# FPGA_MICS_SUP.net
KiCad netlist of a schematic drawn in Altium Designer
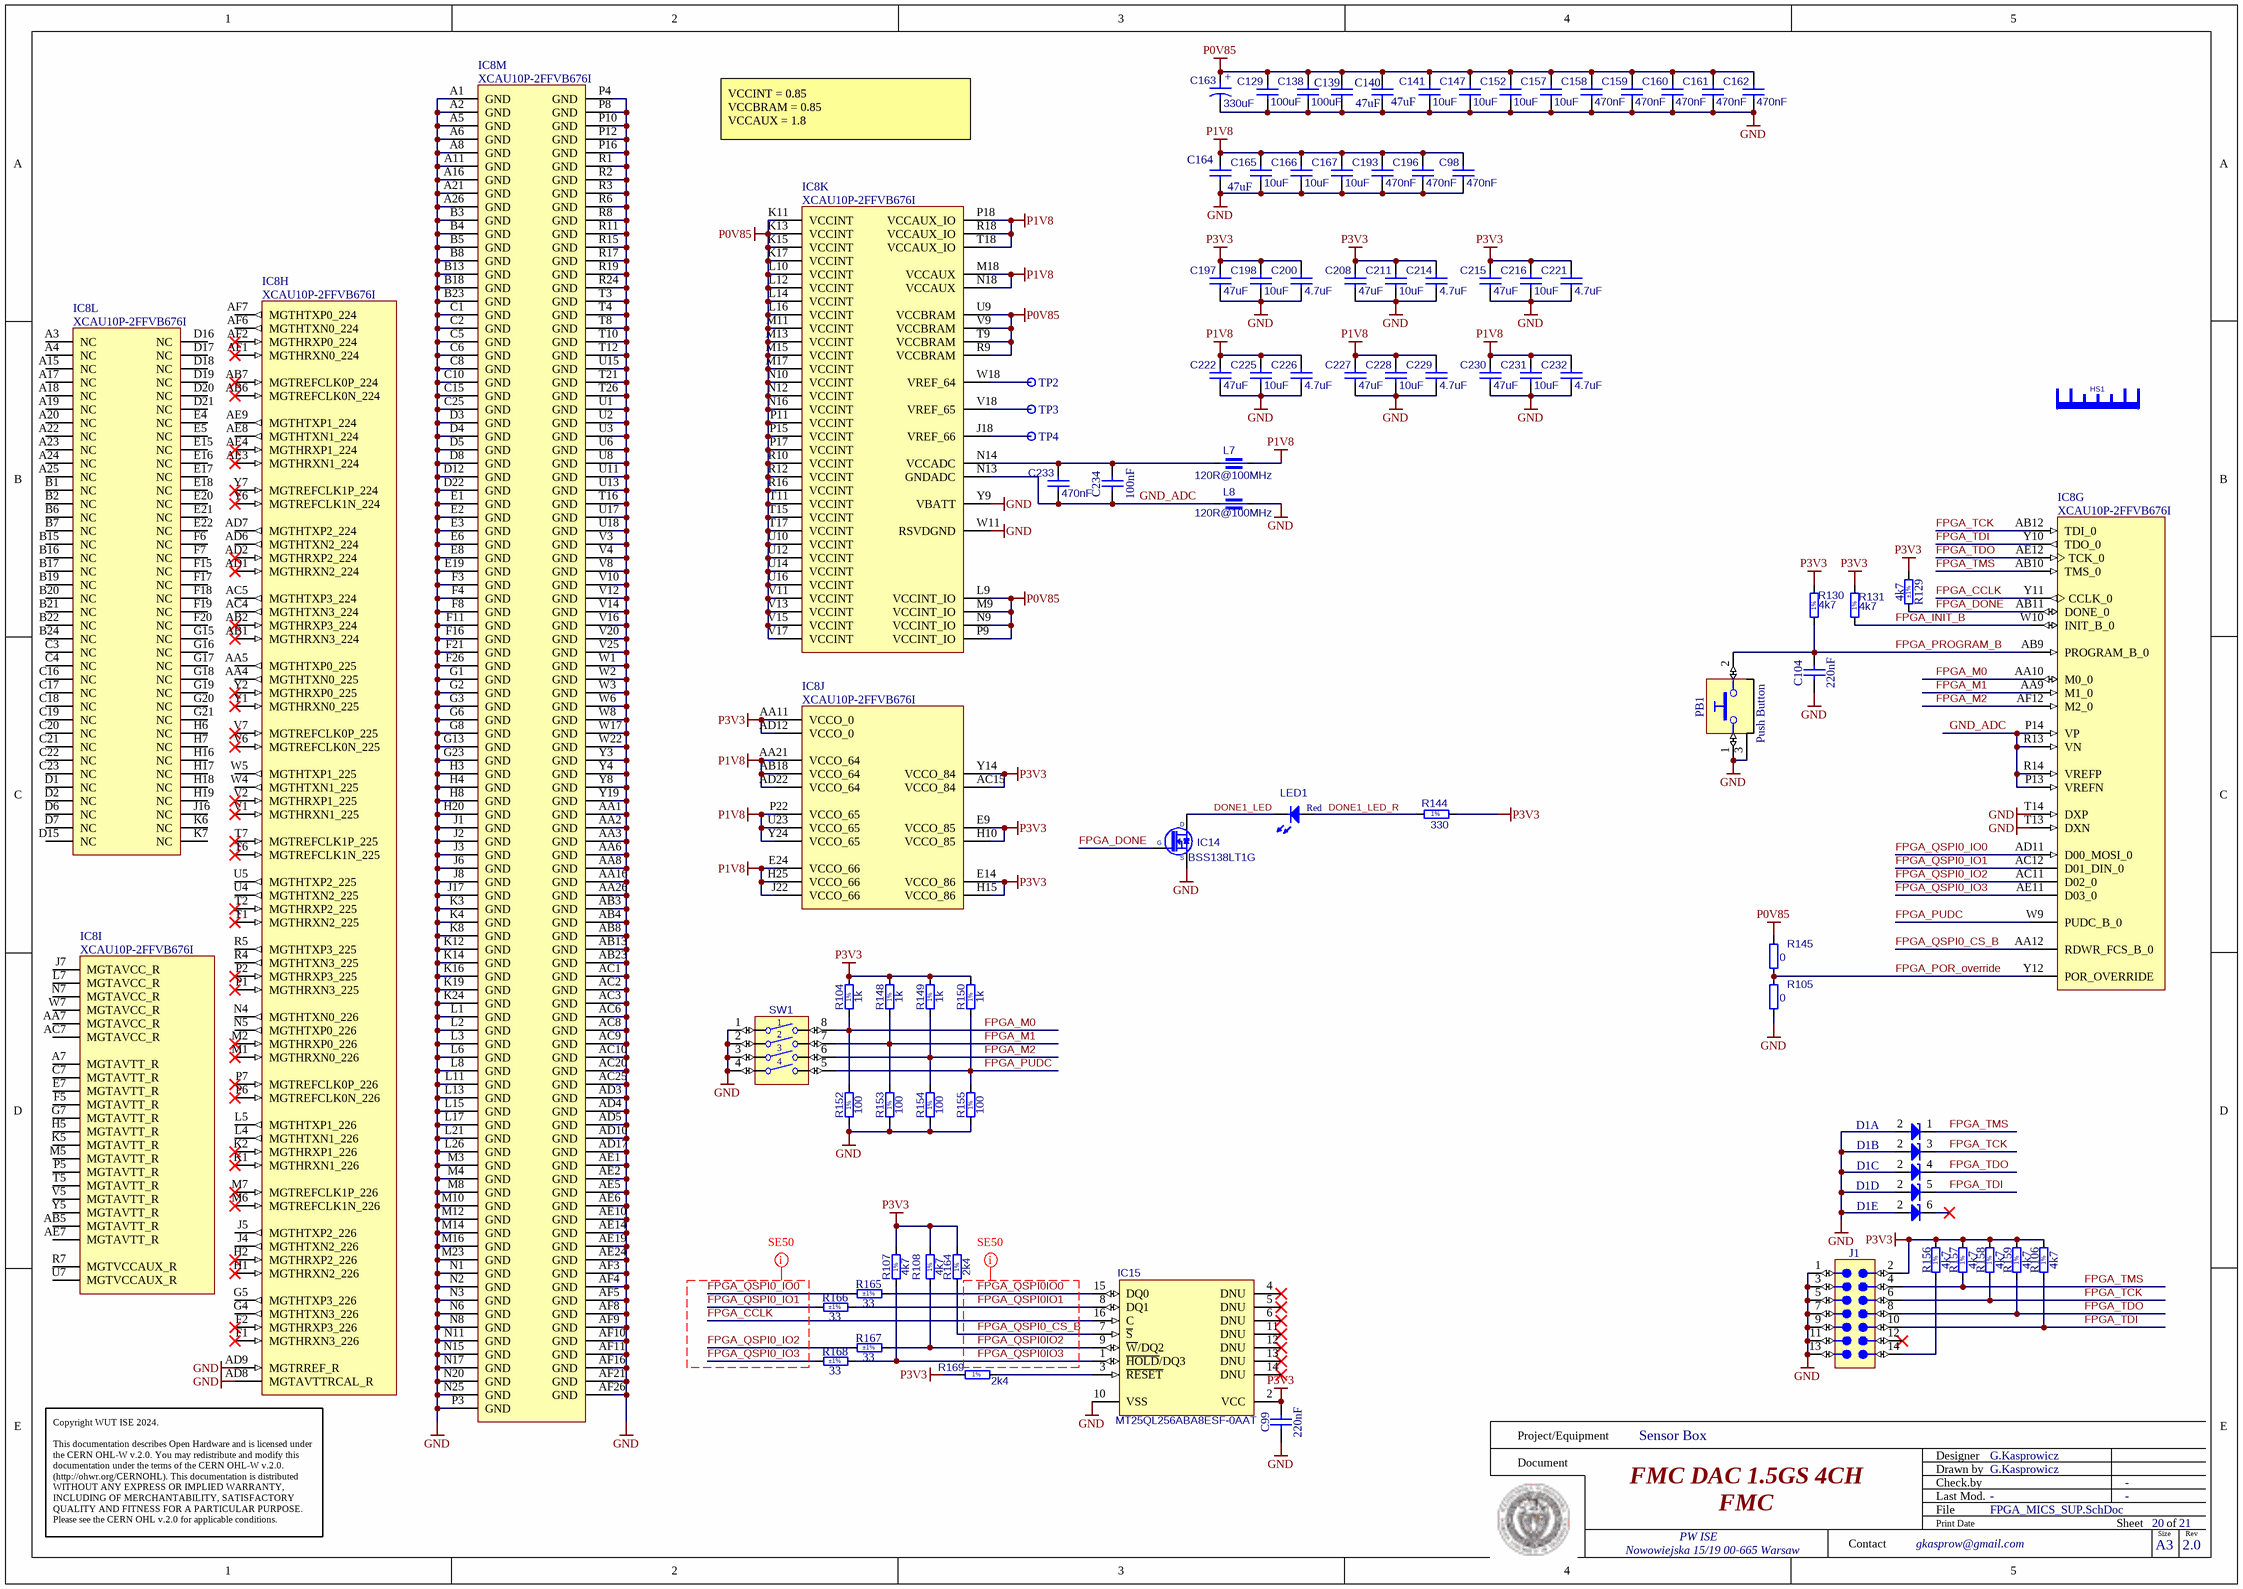
[diagram p0: FPGA_MICS_SUP.SchDoc]

(export (version "E")
  (design (tool "Eeschema 10.0.6"))
  (components
    (comp (ref "C98")
      (value "470nF")
      (footprint "CAPC0603X33N")
      (description "Non-polarised capacitor")
      (fields
        (field (name "PART NUMBER") "CC0201_470NF_4V_20%_X5R")
        (field (name "VOLTAGE") "4V")
        (field (name "AUTHOR") "CERN DEM JLC")
      )
      (libsource (lib "Capacitors") (part "Capacitor - non polarized"))
    )
    (comp (ref "C99")
      (value "220nF")
      (footprint "CAPC1005X55N")
      (description "Non-polarised capacitor")
      (fields
        (field (name "PART NUMBER") "CC0402_220NF_16V_10%_X7R")
        (field (name "VOLTAGE") "16V")
        (field (name "AUTHOR") "CERN DEM JLC")
      )
      (libsource (lib "Capacitors") (part "Capacitor - non polarized"))
    )
    (comp (ref "C104")
      (value "220nF")
      (footprint "CAPC1005X55N")
      (description "Non-polarised capacitor")
      (fields
        (field (name "PART NUMBER") "CC0402_220NF_16V_10%_X7R")
        (field (name "VOLTAGE") "16V")
        (field (name "AUTHOR") "CERN DEM JLC")
      )
      (libsource (lib "Capacitors") (part "Capacitor - non polarized"))
    )
    (comp (ref "C129")
      (value "100uF")
      (footprint "CAPC2013X145N")
      (description "Non-polarised capacitor")
      (fields
        (field (name "PART NUMBER") "CC0805_100UF_4V_20%_X6S_MURATA_GRM21BC80G107ME15")
        (field (name "VOLTAGE") "4V")
        (field (name "AUTHOR") "CERN DEM BC")
      )
      (libsource (lib "Capacitors") (part "Capacitor - non polarized"))
    )
    (comp (ref "C138")
      (value "100uF")
      (footprint "CAPC2013X145N")
      (description "Non-polarised capacitor")
      (fields
        (field (name "PART NUMBER") "CC0805_100UF_4V_20%_X6S_MURATA_GRM21BC80G107ME15")
        (field (name "VOLTAGE") "4V")
        (field (name "AUTHOR") "CERN DEM BC")
      )
      (libsource (lib "Capacitors") (part "Capacitor - non polarized"))
    )
    (comp (ref "C139")
      (value "47uF")
      (footprint "CAPC1608X100N")
      (description "Non-polarised capacitor")
      (fields
        (field (name "MANUFACTURER PART NUMBER") "CC0603_47UF_6.3V_20%_X5R")
        (field (name "MANUFACTURER") "GENERIC")
        (field (name "AUTHOR") "CERN DEM JLC")
      )
      (libsource (lib "Capacitors") (part "Capacitor - non polarized"))
    )
    (comp (ref "C140")
      (value "47uF")
      (footprint "CAPC1608X100N")
      (description "Non-polarised capacitor")
      (fields
        (field (name "MANUFACTURER PART NUMBER") "CC0603_47UF_6.3V_20%_X5R")
        (field (name "MANUFACTURER") "GENERIC")
        (field (name "AUTHOR") "CERN DEM JLC")
      )
      (libsource (lib "Capacitors") (part "Capacitor - non polarized"))
    )
    (comp (ref "C141")
      (value "10uF")
      (footprint "CAPC1005X70N")
      (description "Non-polarised capacitor")
      (fields
        (field (name "PART NUMBER") "CC0402_10UF_6.3V_20%_X5R")
        (field (name "VOLTAGE") "6.3V")
        (field (name "AUTHOR") "CERN DEM JLC")
      )
      (libsource (lib "Capacitors") (part "Capacitor - non polarized"))
    )
    (comp (ref "C147")
      (value "10uF")
      (footprint "CAPC1005X70N")
      (description "Non-polarised capacitor")
      (fields
        (field (name "PART NUMBER") "CC0402_10UF_6.3V_20%_X5R")
        (field (name "VOLTAGE") "6.3V")
        (field (name "AUTHOR") "CERN DEM JLC")
      )
      (libsource (lib "Capacitors") (part "Capacitor - non polarized"))
    )
    (comp (ref "C152")
      (value "10uF")
      (footprint "CAPC1005X70N")
      (description "Non-polarised capacitor")
      (fields
        (field (name "PART NUMBER") "CC0402_10UF_6.3V_20%_X5R")
        (field (name "VOLTAGE") "6.3V")
        (field (name "AUTHOR") "CERN DEM JLC")
      )
      (libsource (lib "Capacitors") (part "Capacitor - non polarized"))
    )
    (comp (ref "C157")
      (value "10uF")
      (footprint "CAPC1005X70N")
      (description "Non-polarised capacitor")
      (fields
        (field (name "PART NUMBER") "CC0402_10UF_6.3V_20%_X5R")
        (field (name "VOLTAGE") "6.3V")
        (field (name "AUTHOR") "CERN DEM JLC")
      )
      (libsource (lib "Capacitors") (part "Capacitor - non polarized"))
    )
    (comp (ref "C158")
      (value "470nF")
      (footprint "CAPC0603X33N")
      (description "Non-polarised capacitor")
      (fields
        (field (name "PART NUMBER") "CC0201_470NF_4V_20%_X5R")
        (field (name "VOLTAGE") "4V")
        (field (name "AUTHOR") "CERN DEM JLC")
      )
      (libsource (lib "Capacitors") (part "Capacitor - non polarized"))
    )
    (comp (ref "C159")
      (value "470nF")
      (footprint "CAPC0603X33N")
      (description "Non-polarised capacitor")
      (fields
        (field (name "PART NUMBER") "CC0201_470NF_4V_20%_X5R")
        (field (name "VOLTAGE") "4V")
        (field (name "AUTHOR") "CERN DEM JLC")
      )
      (libsource (lib "Capacitors") (part "Capacitor - non polarized"))
    )
    (comp (ref "C160")
      (value "470nF")
      (footprint "CAPC0603X33N")
      (description "Non-polarised capacitor")
      (fields
        (field (name "PART NUMBER") "CC0201_470NF_4V_20%_X5R")
        (field (name "VOLTAGE") "4V")
        (field (name "AUTHOR") "CERN DEM JLC")
      )
      (libsource (lib "Capacitors") (part "Capacitor - non polarized"))
    )
    (comp (ref "C161")
      (value "470nF")
      (footprint "CAPC0603X33N")
      (description "Non-polarised capacitor")
      (fields
        (field (name "PART NUMBER") "CC0201_470NF_4V_20%_X5R")
        (field (name "VOLTAGE") "4V")
        (field (name "AUTHOR") "CERN DEM JLC")
      )
      (libsource (lib "Capacitors") (part "Capacitor - non polarized"))
    )
    (comp (ref "C162")
      (value "470nF")
      (footprint "CAPC0603X33N")
      (description "Non-polarised capacitor")
      (fields
        (field (name "PART NUMBER") "CC0201_470NF_4V_20%_X5R")
        (field (name "VOLTAGE") "4V")
        (field (name "AUTHOR") "CERN DEM JLC")
      )
      (libsource (lib "Capacitors") (part "Capacitor - non polarized"))
    )
    (comp (ref "C163")
      (value "330uF")
      (footprint "CAPMP3528X210N")
      (description "Polarised capacitor")
      (fields
        (field (name "PART NUMBER") "CTE3528-21_330UF_2.5V_20%_LESR0015_KEMET_T520")
        (field (name "VOLTAGE") "2.5V")
        (field (name "AUTHOR") "CERN DEM JLC")
      )
      (libsource (lib "Capacitors") (part "Capacitor - polarized"))
    )
    (comp (ref "C164")
      (value "47uF")
      (footprint "CAPC1608X100N")
      (description "Non-polarised capacitor")
      (fields
        (field (name "MANUFACTURER PART NUMBER") "CC0603_47UF_6.3V_20%_X5R")
        (field (name "MANUFACTURER") "GENERIC")
        (field (name "AUTHOR") "CERN DEM JLC")
      )
      (libsource (lib "Capacitors") (part "Capacitor - non polarized"))
    )
    (comp (ref "C165")
      (value "10uF")
      (footprint "CAPC1005X70N")
      (description "Non-polarised capacitor")
      (fields
        (field (name "PART NUMBER") "CC0402_10UF_6.3V_20%_X5R")
        (field (name "VOLTAGE") "6.3V")
        (field (name "AUTHOR") "CERN DEM JLC")
      )
      (libsource (lib "Capacitors") (part "Capacitor - non polarized"))
    )
    (comp (ref "C166")
      (value "10uF")
      (footprint "CAPC1005X70N")
      (description "Non-polarised capacitor")
      (fields
        (field (name "PART NUMBER") "CC0402_10UF_6.3V_20%_X5R")
        (field (name "VOLTAGE") "6.3V")
        (field (name "AUTHOR") "CERN DEM JLC")
      )
      (libsource (lib "Capacitors") (part "Capacitor - non polarized"))
    )
    (comp (ref "C167")
      (value "10uF")
      (footprint "CAPC1005X70N")
      (description "Non-polarised capacitor")
      (fields
        (field (name "PART NUMBER") "CC0402_10UF_6.3V_20%_X5R")
        (field (name "VOLTAGE") "6.3V")
        (field (name "AUTHOR") "CERN DEM JLC")
      )
      (libsource (lib "Capacitors") (part "Capacitor - non polarized"))
    )
    (comp (ref "C193")
      (value "470nF")
      (footprint "CAPC0603X33N")
      (description "Non-polarised capacitor")
      (fields
        (field (name "PART NUMBER") "CC0201_470NF_4V_20%_X5R")
        (field (name "VOLTAGE") "4V")
        (field (name "AUTHOR") "CERN DEM JLC")
      )
      (libsource (lib "Capacitors") (part "Capacitor - non polarized"))
    )
    (comp (ref "C196")
      (value "470nF")
      (footprint "CAPC0603X33N")
      (description "Non-polarised capacitor")
      (fields
        (field (name "PART NUMBER") "CC0201_470NF_4V_20%_X5R")
        (field (name "VOLTAGE") "4V")
        (field (name "AUTHOR") "CERN DEM JLC")
      )
      (libsource (lib "Capacitors") (part "Capacitor - non polarized"))
    )
    (comp (ref "C197")
      (value "47uF")
      (footprint "CAPC1608X100N")
      (description "Non-polarised capacitor")
      (fields
        (field (name "PART NUMBER") "CC0603_47UF_6.3V_20%_X5R")
        (field (name "VOLTAGE") "6.3V")
        (field (name "AUTHOR") "CERN DEM JLC")
      )
      (libsource (lib "Capacitors") (part "Capacitor - non polarized"))
    )
    (comp (ref "C198")
      (value "10uF")
      (footprint "CAPC1005X70N")
      (description "Non-polarised capacitor")
      (fields
        (field (name "PART NUMBER") "CC0402_10UF_6.3V_20%_X5R")
        (field (name "VOLTAGE") "6.3V")
        (field (name "AUTHOR") "CERN DEM JLC")
      )
      (libsource (lib "Capacitors") (part "Capacitor - non polarized"))
    )
    (comp (ref "C200")
      (value "4.7uF")
      (footprint "CAPC1005X61N")
      (description "Non-polarised capacitor")
      (fields
        (field (name "PART NUMBER") "CC0402_4.7UF_4V_20%_X6S_TDK_C1005X6S0G475M050BC")
        (field (name "VOLTAGE") "4V")
        (field (name "AUTHOR") "CERN DEM BC")
      )
      (libsource (lib "Capacitors") (part "Capacitor - non polarized"))
    )
    (comp (ref "C208")
      (value "47uF")
      (footprint "CAPC1608X100N")
      (description "Non-polarised capacitor")
      (fields
        (field (name "PART NUMBER") "CC0603_47UF_6.3V_20%_X5R")
        (field (name "VOLTAGE") "6.3V")
        (field (name "AUTHOR") "CERN DEM JLC")
      )
      (libsource (lib "Capacitors") (part "Capacitor - non polarized"))
    )
    (comp (ref "C211")
      (value "10uF")
      (footprint "CAPC1005X70N")
      (description "Non-polarised capacitor")
      (fields
        (field (name "PART NUMBER") "CC0402_10UF_6.3V_20%_X5R")
        (field (name "VOLTAGE") "6.3V")
        (field (name "AUTHOR") "CERN DEM JLC")
      )
      (libsource (lib "Capacitors") (part "Capacitor - non polarized"))
    )
    (comp (ref "C214")
      (value "4.7uF")
      (footprint "CAPC1005X61N")
      (description "Non-polarised capacitor")
      (fields
        (field (name "PART NUMBER") "CC0402_4.7UF_4V_20%_X6S_TDK_C1005X6S0G475M050BC")
        (field (name "VOLTAGE") "4V")
        (field (name "AUTHOR") "CERN DEM BC")
      )
      (libsource (lib "Capacitors") (part "Capacitor - non polarized"))
    )
    (comp (ref "C215")
      (value "47uF")
      (footprint "CAPC1608X100N")
      (description "Non-polarised capacitor")
      (fields
        (field (name "PART NUMBER") "CC0603_47UF_6.3V_20%_X5R")
        (field (name "VOLTAGE") "6.3V")
        (field (name "AUTHOR") "CERN DEM JLC")
      )
      (libsource (lib "Capacitors") (part "Capacitor - non polarized"))
    )
    (comp (ref "C216")
      (value "10uF")
      (footprint "CAPC1005X70N")
      (description "Non-polarised capacitor")
      (fields
        (field (name "PART NUMBER") "CC0402_10UF_6.3V_20%_X5R")
        (field (name "VOLTAGE") "6.3V")
        (field (name "AUTHOR") "CERN DEM JLC")
      )
      (libsource (lib "Capacitors") (part "Capacitor - non polarized"))
    )
    (comp (ref "C221")
      (value "4.7uF")
      (footprint "CAPC1005X61N")
      (description "Non-polarised capacitor")
      (fields
        (field (name "PART NUMBER") "CC0402_4.7UF_4V_20%_X6S_TDK_C1005X6S0G475M050BC")
        (field (name "VOLTAGE") "4V")
        (field (name "AUTHOR") "CERN DEM BC")
      )
      (libsource (lib "Capacitors") (part "Capacitor - non polarized"))
    )
    (comp (ref "C222")
      (value "47uF")
      (footprint "CAPC1608X100N")
      (description "Non-polarised capacitor")
      (fields
        (field (name "PART NUMBER") "CC0603_47UF_6.3V_20%_X5R")
        (field (name "VOLTAGE") "6.3V")
        (field (name "AUTHOR") "CERN DEM JLC")
      )
      (libsource (lib "Capacitors") (part "Capacitor - non polarized"))
    )
    (comp (ref "C225")
      (value "10uF")
      (footprint "CAPC1005X70N")
      (description "Non-polarised capacitor")
      (fields
        (field (name "PART NUMBER") "CC0402_10UF_6.3V_20%_X5R")
        (field (name "VOLTAGE") "6.3V")
        (field (name "AUTHOR") "CERN DEM JLC")
      )
      (libsource (lib "Capacitors") (part "Capacitor - non polarized"))
    )
    (comp (ref "C226")
      (value "4.7uF")
      (footprint "CAPC1005X61N")
      (description "Non-polarised capacitor")
      (fields
        (field (name "PART NUMBER") "CC0402_4.7UF_4V_20%_X6S_TDK_C1005X6S0G475M050BC")
        (field (name "VOLTAGE") "4V")
        (field (name "AUTHOR") "CERN DEM BC")
      )
      (libsource (lib "Capacitors") (part "Capacitor - non polarized"))
    )
    (comp (ref "C227")
      (value "47uF")
      (footprint "CAPC1608X100N")
      (description "Non-polarised capacitor")
      (fields
        (field (name "PART NUMBER") "CC0603_47UF_6.3V_20%_X5R")
        (field (name "VOLTAGE") "6.3V")
        (field (name "AUTHOR") "CERN DEM JLC")
      )
      (libsource (lib "Capacitors") (part "Capacitor - non polarized"))
    )
    (comp (ref "C228")
      (value "10uF")
      (footprint "CAPC1005X70N")
      (description "Non-polarised capacitor")
      (fields
        (field (name "PART NUMBER") "CC0402_10UF_6.3V_20%_X5R")
        (field (name "VOLTAGE") "6.3V")
        (field (name "AUTHOR") "CERN DEM JLC")
      )
      (libsource (lib "Capacitors") (part "Capacitor - non polarized"))
    )
    (comp (ref "C229")
      (value "4.7uF")
      (footprint "CAPC1005X61N")
      (description "Non-polarised capacitor")
      (fields
        (field (name "PART NUMBER") "CC0402_4.7UF_4V_20%_X6S_TDK_C1005X6S0G475M050BC")
        (field (name "VOLTAGE") "4V")
        (field (name "AUTHOR") "CERN DEM BC")
      )
      (libsource (lib "Capacitors") (part "Capacitor - non polarized"))
    )
    (comp (ref "C230")
      (value "47uF")
      (footprint "CAPC1608X100N")
      (description "Non-polarised capacitor")
      (fields
        (field (name "PART NUMBER") "CC0603_47UF_6.3V_20%_X5R")
        (field (name "VOLTAGE") "6.3V")
        (field (name "AUTHOR") "CERN DEM JLC")
      )
      (libsource (lib "Capacitors") (part "Capacitor - non polarized"))
    )
    (comp (ref "C231")
      (value "10uF")
      (footprint "CAPC1005X70N")
      (description "Non-polarised capacitor")
      (fields
        (field (name "PART NUMBER") "CC0402_10UF_6.3V_20%_X5R")
        (field (name "VOLTAGE") "6.3V")
        (field (name "AUTHOR") "CERN DEM JLC")
      )
      (libsource (lib "Capacitors") (part "Capacitor - non polarized"))
    )
    (comp (ref "C232")
      (value "4.7uF")
      (footprint "CAPC1005X61N")
      (description "Non-polarised capacitor")
      (fields
        (field (name "PART NUMBER") "CC0402_4.7UF_4V_20%_X6S_TDK_C1005X6S0G475M050BC")
        (field (name "VOLTAGE") "4V")
        (field (name "AUTHOR") "CERN DEM BC")
      )
      (libsource (lib "Capacitors") (part "Capacitor - non polarized"))
    )
    (comp (ref "C233")
      (value "470nF")
      (footprint "CAPC0603X33N")
      (description "Non-polarised capacitor")
      (fields
        (field (name "PART NUMBER") "CC0201_470NF_4V_20%_X5R")
        (field (name "VOLTAGE") "4V")
        (field (name "AUTHOR") "CERN DEM JLC")
      )
      (libsource (lib "Capacitors") (part "Capacitor - non polarized"))
    )
    (comp (ref "C234")
      (value "100nF")
      (footprint "CAPC1005X55N")
      (description "Non-polarised capacitor")
      (fields
        (field (name "PART NUMBER") "CC0402_100NF_16V_10%_X5R")
        (field (name "VOLTAGE") "16V")
        (field (name "AUTHOR") "CERN DEM JLC")
      )
      (libsource (lib "Capacitors") (part "Capacitor - non polarized"))
    )
    (comp (ref "D1")
      (value "PESD3V3L5UY")
      (footprint "SOT65P210X110-6N")
      (description "Fivefold ESD Protection Diode Arrays")
      (fields
        (field (name "VOLTAGE") "3.3V")
        (field (name "POWER") "200W")
        (field (name "AUTHOR") "CERN DEM WB")
      )
      (libsource (lib "ICs And Semiconductors") (part "PESD Array 5diodes 6pins Common anode2"))
    )
    (comp (ref "HS1")
      (value "Heat Sink 2 Pads")
      (footprint "HSINK_WAKEFIELD_960-29-18-D-AB-0")
      (description "Heat Sink With 2 pads")
      (fields
        (field (name "PART NUMBER") "HSINK_WAKEFIELD_960-29-12-D-AB-0")
        (field (name "MANUFACTURER") "WAKEFIELD-VETTE")
        (field (name "AUTHOR") "CERN DEM BC")
      )
      (libsource (lib "Eletro-mechanical") (part "Heat Sink 2 Pads"))
    )
    (comp (ref "IC8")
      (value "XCAU10P-2FFVB676I")
      (footprint "BGA676C100P26X26_2700X2700X350")
      (description "Artix UltraScale + Field Programmable Gate Array (FPGA), 676-Pin BGA, Industrial Grade")
      (fields (field (name "MANUFACTURER") "AMD") (field (name "AUTHOR") "CERN DEM HF"))
      (libsource (lib "ICs And Semiconductors") (part "XCAU10P-2FFVB676I"))
    )
    (comp (ref "IC14")
      (value "BSS138LT1G")
      (footprint "SOT95P240X110-3N")
      (description "N-CHANNEL MOSFET WITH DIODE")
      (fields (field (name "MANUFACTURER") "ON SEMICONDUCTOR") (field (name "AUTHOR") "CERN DEM JLC"))
      (libsource (lib "ICs And Semiconductors") (part "N-MOSFET-D 1G 2S 3D"))
    )
    (comp (ref "IC15")
      (value "MT25QL256ABA8ESF-0AAT")
      (footprint "SOIC127P1030X265-16N")
      (description "256Mbit (32MB), 2.7V-3.6V, Multiple I/O Serial NOR Flash Memory,with Reset# & Hold#")
      (fields (field (name "MANUFACTURER") "MICRON TECHNOLOGY") (field (name "AUTHOR") "CERN DEM JLC"))
      (libsource (lib "ICs And Semiconductors") (part "MT25QL256ABA8ESF"))
    )
    (comp (ref "J1")
      (value "~")
      (footprint "MOLEX_87832-1420")
      (description "Connector 14 Male")
      (fields
        (field (name "PART NUMBER") "MOLEX_87832-1420")
        (field (name "MANUFACTURER") "MOLEX")
        (field (name "AUTHOR") "CERN DEM JLC")
      )
      (libsource (lib "Connectors") (part "Connector 14 Male"))
    )
    (comp (ref "L7")
      (value "120R@100MHz")
      (footprint "INDC1608X95N")
      (fields
        (field (name "PART NUMBER") "IND0603_MURATA_BLM18PG121SN1D")
        (field (name "POWER") "2A")
        (field (name "MANUFACTURER") "MURATA")
        (field (name "AUTHOR") "CERN DEM BC")
      )
      (libsource (lib "Inductors & Transformers") (part "Ferrite Bead"))
    )
    (comp (ref "L8")
      (value "120R@100MHz")
      (footprint "INDC1608X95N")
      (fields
        (field (name "PART NUMBER") "IND0603_MURATA_BLM18PG121SN1D")
        (field (name "POWER") "2A")
        (field (name "MANUFACTURER") "MURATA")
        (field (name "AUTHOR") "CERN DEM BC")
      )
      (libsource (lib "Inductors & Transformers") (part "Ferrite Bead"))
    )
    (comp (ref "LED1")
      (value "Red")
      (footprint "LED_KINGBRIGHT_KPH-1608SURCK")
      (description "LED Red 1C 2A")
      (fields
        (field (name "PART NUMBER") "LED_KINGBRIGHT_KPH-1608SURCK")
        (field (name "MANUFACTURER") "KINGBRIGHT")
        (field (name "AUTHOR") "CERN DEM JLC")
      )
      (libsource (lib "ICs And Semiconductors") (part "LED Red 1C 2A"))
    )
    (comp (ref "PB1")
      (value "Push Button")
      (footprint "PB_OMRON_B3U-1100P")
      (description "Push-Button Switch SPDT")
      (fields
        (field (name "PART NUMBER") "PB_OMRON_B3U-1100P")
        (field (name "MANUFACTURER") "OMRON")
        (field (name "AUTHOR") "CERN DEM JLC")
      )
      (libsource (lib "Eletro-mechanical") (part "PB SPST 1NO-2NO 3CASE"))
    )
    (comp (ref "R104")
      (value "1k")
      (footprint "RESC1005X40N")
      (description "Resistor - 1%")
      (fields
        (field (name "PART NUMBER") "R0402_1K_1%_0.0625W_100PPM")
        (field (name "POWER") "0.0625W")
        (field (name "AUTHOR") "CERN DEM JLC")
      )
      (libsource (lib "Resistors") (part "Resistor - 1%"))
    )
    (comp (ref "R105")
      (value "0")
      (footprint "RESC1005X40N")
      (description "Resistor")
      (fields
        (field (name "MANUFACTURER PART NUMBER") "R0402_0R_JUMPER")
        (field (name "MANUFACTURER") "GENERIC")
        (field (name "AUTHOR") "CERN DEM JLC")
      )
      (libsource (lib "Resistors") (part "Resistor"))
    )
    (comp (ref "R106")
      (value "4k7")
      (footprint "RESC1005X40N")
      (description "Resistor - 1%")
      (fields
        (field (name "PART NUMBER") "R0402_4K7_1%_0.0625W_100PPM")
        (field (name "POWER") "0.0625W")
        (field (name "AUTHOR") "CERN DEM JLC")
      )
      (libsource (lib "Resistors") (part "Resistor - 1%"))
    )
    (comp (ref "R107")
      (value "4k7")
      (footprint "RESC1005X40N")
      (description "Resistor - 1%")
      (fields
        (field (name "MANUFACTURER PART NUMBER") "R0402_4K7_1%_0.0625W_100PPM")
        (field (name "MANUFACTURER") "GENERIC")
        (field (name "AUTHOR") "CERN DEM JLC")
      )
      (libsource (lib "Resistors") (part "Resistor - 1%"))
    )
    (comp (ref "R108")
      (value "4k7")
      (footprint "RESC1005X40N")
      (description "Resistor - 1%")
      (fields
        (field (name "MANUFACTURER PART NUMBER") "R0402_4K7_1%_0.0625W_100PPM")
        (field (name "MANUFACTURER") "GENERIC")
        (field (name "AUTHOR") "CERN DEM JLC")
      )
      (libsource (lib "Resistors") (part "Resistor - 1%"))
    )
    (comp (ref "R129")
      (value "4k7")
      (footprint "RESC1005X40N")
      (description "Resistor - 1%")
      (fields
        (field (name "TOLERANCE") "±1%")
        (field (name "PART NUMBER") "R0402_4K7_1%_0.0625W_100PPM")
        (field (name "POWER") "0.0625W")
        (field (name "AUTHOR") "CERN DEM JLC")
      )
      (libsource (lib "Resistors") (part "Resistor - 1%"))
    )
    (comp (ref "R130")
      (value "4k7")
      (footprint "RESC1005X40N")
      (description "Resistor - 1%")
      (fields
        (field (name "MANUFACTURER PART NUMBER") "R0402_4K7_1%_0.0625W_100PPM")
        (field (name "MANUFACTURER") "GENERIC")
        (field (name "AUTHOR") "CERN DEM JLC")
      )
      (libsource (lib "Resistors") (part "Resistor - 1%"))
    )
    (comp (ref "R131")
      (value "4k7")
      (footprint "RESC1005X40N")
      (description "Resistor - 1%")
      (fields
        (field (name "MANUFACTURER PART NUMBER") "R0402_4K7_1%_0.0625W_100PPM")
        (field (name "MANUFACTURER") "GENERIC")
        (field (name "AUTHOR") "CERN DEM JLC")
      )
      (libsource (lib "Resistors") (part "Resistor - 1%"))
    )
    (comp (ref "R144")
      (value "330")
      (footprint "RESC1005X40N")
      (description "Resistor - 1%")
      (fields
        (field (name "PART NUMBER") "R0402_330R_1%_0.0625W_100PPM")
        (field (name "POWER") "0.0625W")
        (field (name "AUTHOR") "CERN DEM JLC")
      )
      (libsource (lib "Resistors") (part "Resistor - 1%"))
    )
    (comp (ref "R145")
      (value "0")
      (footprint "RESC1005X40N")
      (description "Resistor")
      (fields
        (field (name "MANUFACTURER PART NUMBER") "R0402_0R_JUMPER")
        (field (name "MANUFACTURER") "GENERIC")
        (field (name "AUTHOR") "CERN DEM JLC")
      )
      (libsource (lib "Resistors") (part "Resistor"))
    )
    (comp (ref "R148")
      (value "1k")
      (footprint "RESC1005X40N")
      (description "Resistor - 1%")
      (fields
        (field (name "PART NUMBER") "R0402_1K_1%_0.0625W_100PPM")
        (field (name "POWER") "0.0625W")
        (field (name "AUTHOR") "CERN DEM JLC")
      )
      (libsource (lib "Resistors") (part "Resistor - 1%"))
    )
    (comp (ref "R149")
      (value "1k")
      (footprint "RESC1005X40N")
      (description "Resistor - 1%")
      (fields
        (field (name "PART NUMBER") "R0402_1K_1%_0.0625W_100PPM")
        (field (name "POWER") "0.0625W")
        (field (name "AUTHOR") "CERN DEM JLC")
      )
      (libsource (lib "Resistors") (part "Resistor - 1%"))
    )
    (comp (ref "R150")
      (value "1k")
      (footprint "RESC1005X40N")
      (description "Resistor - 1%")
      (fields
        (field (name "PART NUMBER") "R0402_1K_1%_0.0625W_100PPM")
        (field (name "POWER") "0.0625W")
        (field (name "AUTHOR") "CERN DEM JLC")
      )
      (libsource (lib "Resistors") (part "Resistor - 1%"))
    )
    (comp (ref "R152")
      (value "100")
      (footprint "RESC1005X40N")
      (description "Resistor - 1%")
      (fields
        (field (name "PART NUMBER") "R0402_100R_1%_0.0625W_100PPM")
        (field (name "POWER") "0.0625W")
        (field (name "AUTHOR") "CERN DEM JLC")
      )
      (libsource (lib "Resistors") (part "Resistor - 1%"))
    )
    (comp (ref "R153")
      (value "100")
      (footprint "RESC1005X40N")
      (description "Resistor - 1%")
      (fields
        (field (name "PART NUMBER") "R0402_100R_1%_0.0625W_100PPM")
        (field (name "POWER") "0.0625W")
        (field (name "AUTHOR") "CERN DEM JLC")
      )
      (libsource (lib "Resistors") (part "Resistor - 1%"))
    )
    (comp (ref "R154")
      (value "100")
      (footprint "RESC1005X40N")
      (description "Resistor - 1%")
      (fields
        (field (name "PART NUMBER") "R0402_100R_1%_0.0625W_100PPM")
        (field (name "POWER") "0.0625W")
        (field (name "AUTHOR") "CERN DEM JLC")
      )
      (libsource (lib "Resistors") (part "Resistor - 1%"))
    )
    (comp (ref "R155")
      (value "100")
      (footprint "RESC1005X40N")
      (description "Resistor - 1%")
      (fields
        (field (name "PART NUMBER") "R0402_100R_1%_0.0625W_100PPM")
        (field (name "POWER") "0.0625W")
        (field (name "AUTHOR") "CERN DEM JLC")
      )
      (libsource (lib "Resistors") (part "Resistor - 1%"))
    )
    (comp (ref "R156")
      (value "4k7")
      (footprint "RESC1005X40N")
      (description "Resistor - 1%")
      (fields
        (field (name "PART NUMBER") "R0402_4K7_1%_0.0625W_100PPM")
        (field (name "POWER") "0.0625W")
        (field (name "AUTHOR") "CERN DEM JLC")
      )
      (libsource (lib "Resistors") (part "Resistor - 1%"))
    )
    (comp (ref "R157")
      (value "4k7")
      (footprint "RESC1005X40N")
      (description "Resistor - 1%")
      (fields
        (field (name "PART NUMBER") "R0402_4K7_1%_0.0625W_100PPM")
        (field (name "POWER") "0.0625W")
        (field (name "AUTHOR") "CERN DEM JLC")
      )
      (libsource (lib "Resistors") (part "Resistor - 1%"))
    )
    (comp (ref "R158")
      (value "4k7")
      (footprint "RESC1005X40N")
      (description "Resistor - 1%")
      (fields
        (field (name "PART NUMBER") "R0402_4K7_1%_0.0625W_100PPM")
        (field (name "POWER") "0.0625W")
        (field (name "AUTHOR") "CERN DEM JLC")
      )
      (libsource (lib "Resistors") (part "Resistor - 1%"))
    )
    (comp (ref "R159")
      (value "4k7")
      (footprint "RESC1005X40N")
      (description "Resistor - 1%")
      (fields
        (field (name "PART NUMBER") "R0402_4K7_1%_0.0625W_100PPM")
        (field (name "POWER") "0.0625W")
        (field (name "AUTHOR") "CERN DEM JLC")
      )
      (libsource (lib "Resistors") (part "Resistor - 1%"))
    )
    (comp (ref "R164")
      (value "2k4")
      (footprint "RESC1005X40N")
      (description "Resistor - 1%")
      (fields
        (field (name "MANUFACTURER PART NUMBER") "R0402_2K4_1%_0.0625W_100PPM")
        (field (name "MANUFACTURER") "GENERIC")
        (field (name "AUTHOR") "CERN DEM JLC")
      )
      (libsource (lib "Resistors") (part "Resistor - 1%"))
    )
    (comp (ref "R165")
      (value "33")
      (footprint "RESC1005X40N")
      (description "Resistor - 1%")
      (fields
        (field (name "TOLERANCE") "±1%")
        (field (name "PART NUMBER") "R0402_33R_1%_0.0625W_100PPM")
        (field (name "POWER") "0.0625W")
        (field (name "AUTHOR") "CERN DEM JLC")
      )
      (libsource (lib "Resistors") (part "Resistor - 1%"))
    )
    (comp (ref "R166")
      (value "33")
      (footprint "RESC1005X40N")
      (description "Resistor - 1%")
      (fields
        (field (name "TOLERANCE") "±1%")
        (field (name "PART NUMBER") "R0402_33R_1%_0.0625W_100PPM")
        (field (name "POWER") "0.0625W")
        (field (name "AUTHOR") "CERN DEM JLC")
      )
      (libsource (lib "Resistors") (part "Resistor - 1%"))
    )
    (comp (ref "R167")
      (value "33")
      (footprint "RESC1005X40N")
      (description "Resistor - 1%")
      (fields
        (field (name "TOLERANCE") "±1%")
        (field (name "PART NUMBER") "R0402_33R_1%_0.0625W_100PPM")
        (field (name "POWER") "0.0625W")
        (field (name "AUTHOR") "CERN DEM JLC")
      )
      (libsource (lib "Resistors") (part "Resistor - 1%"))
    )
    (comp (ref "R168")
      (value "33")
      (footprint "RESC1005X40N")
      (description "Resistor - 1%")
      (fields
        (field (name "TOLERANCE") "±1%")
        (field (name "PART NUMBER") "R0402_33R_1%_0.0625W_100PPM")
        (field (name "POWER") "0.0625W")
        (field (name "AUTHOR") "CERN DEM JLC")
      )
      (libsource (lib "Resistors") (part "Resistor - 1%"))
    )
    (comp (ref "R169")
      (value "2k4")
      (footprint "RESC1005X40N")
      (description "Resistor - 1%")
      (fields
        (field (name "MANUFACTURER PART NUMBER") "R0402_2K4_1%_0.0625W_100PPM")
        (field (name "MANUFACTURER") "GENERIC")
        (field (name "AUTHOR") "CERN DEM JLC")
      )
      (libsource (lib "Resistors") (part "Resistor - 1%"))
    )
    (comp (ref "SW1")
      (value "Switch")
      (footprint "SW_TYCO_1571983-4")
      (description "4 Ways SPST DIP Switch")
      (fields
        (field (name "PART NUMBER") "SW_TYCO_1571983-4")
        (field (name "MANUFACTURER") "TYCO")
        (field (name "AUTHOR") "CERN DEM JLC")
      )
      (libsource (lib "Eletro-mechanical") (part "SW 4x SPST DIP Switch"))
    )
    (comp (ref "TP2")
      (value "Test Point")
      (footprint "TPS127")
      (fields (field (name "PART NUMBER") "SMD_PAD_1.27X1.27MM") (field (name "AUTHOR") "CERN DEM JLC"))
      (libsource (lib "Eletro-mechanical") (part "Test Point"))
    )
    (comp (ref "TP3")
      (value "Test Point")
      (footprint "TPS127")
      (fields (field (name "PART NUMBER") "SMD_PAD_1.27X1.27MM") (field (name "AUTHOR") "CERN DEM JLC"))
      (libsource (lib "Eletro-mechanical") (part "Test Point"))
    )
    (comp (ref "TP4")
      (value "Test Point")
      (footprint "TPS127")
      (fields (field (name "PART NUMBER") "SMD_PAD_1.27X1.27MM") (field (name "AUTHOR") "CERN DEM JLC"))
      (libsource (lib "Eletro-mechanical") (part "Test Point"))
    )
  )
  (nets
    (net (code "1") (name "/DONE1_LED") (class "Default")
      (node (ref "IC14") (pin "3") (pinfunction "D_3") (pintype "passive"))
      (node (ref "LED1") (pin "1") (pinfunction "C_1") (pintype "passive"))
    )
    (net (code "2") (name "/DONE1_LED_R") (class "Default")
      (node (ref "LED1") (pin "2") (pinfunction "A_2") (pintype "passive"))
      (node (ref "R144") (pin "1") (pinfunction "1_1") (pintype "passive"))
    )
    (net (code "3") (name "/FPGA_CCLK") (class "Default")
      (node (ref "IC15") (pin "16") (pinfunction "C_16") (pintype "input"))
      (node (ref "IC8") (pin "Y11") (pinfunction "CCLK_0_Y11") (pintype "output"))
    )
    (net (code "4") (name "/FPGA_DONE") (class "Default")
      (node (ref "IC14") (pin "1") (pinfunction "G_1") (pintype "passive"))
      (node (ref "IC8") (pin "AB11") (pinfunction "DONE_0_AB11") (pintype "bidirectional"))
      (node (ref "R129") (pin "1") (pinfunction "1_1") (pintype "passive"))
    )
    (net (code "5") (name "/FPGA_INIT_B") (class "Default")
      (node (ref "IC8") (pin "W10") (pinfunction "INIT_B_0_W10") (pintype "bidirectional"))
      (node (ref "R131") (pin "1") (pinfunction "1_1") (pintype "passive"))
    )
    (net (code "6") (name "/FPGA_M0") (class "Default")
      (node (ref "IC8") (pin "AA10") (pinfunction "M0_0_AA10") (pintype "bidirectional"))
      (node (ref "R104") (pin "1") (pinfunction "1_1") (pintype "passive"))
      (node (ref "R152") (pin "2") (pinfunction "2_2") (pintype "passive"))
      (node (ref "SW1") (pin "8") (pinfunction "8_8") (pintype "bidirectional"))
    )
    (net (code "7") (name "/FPGA_M1") (class "Default")
      (node (ref "IC8") (pin "AA9") (pinfunction "M1_0_AA9") (pintype "input"))
      (node (ref "R148") (pin "1") (pinfunction "1_1") (pintype "passive"))
      (node (ref "R153") (pin "2") (pinfunction "2_2") (pintype "passive"))
      (node (ref "SW1") (pin "7") (pinfunction "7_7") (pintype "bidirectional"))
    )
    (net (code "8") (name "/FPGA_M2") (class "Default")
      (node (ref "IC8") (pin "AF12") (pinfunction "M2_0_AF12") (pintype "input"))
      (node (ref "R149") (pin "1") (pinfunction "1_1") (pintype "passive"))
      (node (ref "R154") (pin "2") (pinfunction "2_2") (pintype "passive"))
      (node (ref "SW1") (pin "6") (pinfunction "6_6") (pintype "bidirectional"))
    )
    (net (code "9") (name "/FPGA_POR_override") (class "Default")
      (node (ref "IC8") (pin "Y12") (pinfunction "POR_OVERRIDE_Y12") (pintype "passive"))
      (node (ref "R105") (pin "2") (pinfunction "2_2") (pintype "passive"))
      (node (ref "R145") (pin "1") (pinfunction "1_1") (pintype "passive"))
    )
    (net (code "10") (name "/FPGA_PROGRAM_B") (class "Default")
      (node (ref "C104") (pin "2") (pinfunction "2_2") (pintype "passive"))
      (node (ref "IC8") (pin "AB9") (pinfunction "PROGRAM_B_0_AB9") (pintype "input"))
      (node (ref "PB1") (pin "2") (pinfunction "2_2") (pintype "bidirectional"))
      (node (ref "R130") (pin "1") (pinfunction "1_1") (pintype "passive"))
    )
    (net (code "11") (name "/FPGA_PUDC") (class "Default")
      (node (ref "IC8") (pin "W9") (pinfunction "PUDC_B_0_W9") (pintype "passive"))
      (node (ref "R150") (pin "1") (pinfunction "1_1") (pintype "passive"))
      (node (ref "R155") (pin "2") (pinfunction "2_2") (pintype "passive"))
      (node (ref "SW1") (pin "5") (pinfunction "5_5") (pintype "bidirectional"))
    )
    (net (code "12") (name "/FPGA_QSPI0IO0") (class "Default")
      (node (ref "IC15") (pin "15") (pinfunction "DQ0_15") (pintype "bidirectional"))
      (node (ref "R165") (pin "2") (pinfunction "2_2") (pintype "passive"))
    )
    (net (code "13") (name "/FPGA_QSPI0IO1") (class "Default")
      (node (ref "IC15") (pin "8") (pinfunction "DQ1_8") (pintype "bidirectional"))
      (node (ref "R166") (pin "2") (pinfunction "2_2") (pintype "passive"))
    )
    (net (code "14") (name "/FPGA_QSPI0IO2") (class "Default")
      (node (ref "IC15") (pin "9") (pinfunction "~{W}/DQ2_9") (pintype "bidirectional"))
      (node (ref "R108") (pin "1") (pinfunction "1_1") (pintype "passive"))
      (node (ref "R167") (pin "2") (pinfunction "2_2") (pintype "passive"))
    )
    (net (code "15") (name "/FPGA_QSPI0IO3") (class "Default")
      (node (ref "IC15") (pin "1") (pinfunction "~{HOLD}/DQ3_1") (pintype "bidirectional"))
      (node (ref "R107") (pin "1") (pinfunction "1_1") (pintype "passive"))
      (node (ref "R168") (pin "2") (pinfunction "2_2") (pintype "passive"))
    )
    (net (code "16") (name "/FPGA_QSPI0_CS_B") (class "Default")
      (node (ref "IC15") (pin "7") (pinfunction "~{S}_7") (pintype "input"))
      (node (ref "IC8") (pin "AA12") (pinfunction "RDWR_FCS_B_0_AA12") (pintype "passive"))
      (node (ref "R164") (pin "1") (pinfunction "1_1") (pintype "passive"))
    )
    (net (code "17") (name "/FPGA_QSPI0_IO0") (class "Default")
      (node (ref "IC8") (pin "AD11") (pinfunction "D00_MOSI_0_AD11") (pintype "input"))
      (node (ref "R165") (pin "1") (pinfunction "1_1") (pintype "passive"))
    )
    (net (code "18") (name "/FPGA_QSPI0_IO1") (class "Default")
      (node (ref "IC8") (pin "AC12") (pinfunction "D01_DIN_0_AC12") (pintype "passive"))
      (node (ref "R166") (pin "1") (pinfunction "1_1") (pintype "passive"))
    )
    (net (code "19") (name "/FPGA_QSPI0_IO2") (class "Default")
      (node (ref "IC8") (pin "AC11") (pinfunction "D02_0_AC11") (pintype "passive"))
      (node (ref "R167") (pin "1") (pinfunction "1_1") (pintype "passive"))
    )
    (net (code "20") (name "/FPGA_QSPI0_IO3") (class "Default")
      (node (ref "IC8") (pin "AE11") (pinfunction "D03_0_AE11") (pintype "passive"))
      (node (ref "R168") (pin "1") (pinfunction "1_1") (pintype "passive"))
    )
    (net (code "21") (name "/FPGA_TCK") (class "Default")
      (node (ref "D1") (pin "3") (pinfunction "C_3") (pintype "passive"))
      (node (ref "IC8") (pin "AB12") (pinfunction "TDI_0_AB12") (pintype "input"))
      (node (ref "J1") (pin "6") (pinfunction "6_6") (pintype "bidirectional"))
      (node (ref "R158") (pin "1") (pinfunction "1_1") (pintype "passive"))
    )
    (net (code "22") (name "/FPGA_TDI") (class "Default")
      (node (ref "D1") (pin "5") (pinfunction "C_5") (pintype "passive"))
      (node (ref "IC8") (pin "Y10") (pinfunction "TDO_0_Y10") (pintype "output"))
      (node (ref "J1") (pin "10") (pinfunction "10_10") (pintype "bidirectional"))
      (node (ref "R106") (pin "1") (pinfunction "1_1") (pintype "passive"))
    )
    (net (code "23") (name "/FPGA_TDO") (class "Default")
      (node (ref "D1") (pin "4") (pinfunction "C_4") (pintype "passive"))
      (node (ref "IC8") (pin "AE12") (pinfunction "TCK_0_AE12") (pintype "input"))
      (node (ref "J1") (pin "8") (pinfunction "8_8") (pintype "bidirectional"))
      (node (ref "R159") (pin "1") (pinfunction "1_1") (pintype "passive"))
    )
    (net (code "24") (name "/FPGA_TMS") (class "Default")
      (node (ref "D1") (pin "1") (pinfunction "C_1") (pintype "passive"))
      (node (ref "IC8") (pin "AB10") (pinfunction "TMS_0_AB10") (pintype "input"))
      (node (ref "J1") (pin "4") (pinfunction "4_4") (pintype "bidirectional"))
      (node (ref "R157") (pin "1") (pinfunction "1_1") (pintype "passive"))
    )
    (net (code "25") (name "/GND_ADC") (class "Default")
      (node (ref "C233") (pin "1") (pinfunction "1_1") (pintype "passive"))
      (node (ref "C234") (pin "1") (pinfunction "1_1") (pintype "passive"))
      (node (ref "IC8") (pin "N13") (pinfunction "GNDADC_N13") (pintype "power_in"))
      (node (ref "IC8") (pin "P13") (pinfunction "VREFN_P13") (pintype "input"))
      (node (ref "IC8") (pin "P14") (pinfunction "VP_P14") (pintype "input"))
      (node (ref "IC8") (pin "R13") (pinfunction "VN_R13") (pintype "input"))
      (node (ref "IC8") (pin "R14") (pinfunction "VREFP_R14") (pintype "input"))
      (node (ref "L8") (pin "1") (pinfunction "1_1") (pintype "passive"))
    )
    (net (code "26") (name "GND") (class "Default")
      (node (ref "C104") (pin "1") (pinfunction "1_1") (pintype "passive"))
      (node (ref "C129") (pin "1") (pinfunction "1_1") (pintype "passive"))
      (node (ref "C138") (pin "1") (pinfunction "1_1") (pintype "passive"))
      (node (ref "C139") (pin "1") (pinfunction "1_1") (pintype "passive"))
      (node (ref "C140") (pin "1") (pinfunction "1_1") (pintype "passive"))
      (node (ref "C141") (pin "1") (pinfunction "1_1") (pintype "passive"))
      (node (ref "C147") (pin "1") (pinfunction "1_1") (pintype "passive"))
      (node (ref "C152") (pin "1") (pinfunction "1_1") (pintype "passive"))
      (node (ref "C157") (pin "1") (pinfunction "1_1") (pintype "passive"))
      (node (ref "C158") (pin "1") (pinfunction "1_1") (pintype "passive"))
      (node (ref "C159") (pin "1") (pinfunction "1_1") (pintype "passive"))
      (node (ref "C160") (pin "1") (pinfunction "1_1") (pintype "passive"))
      (node (ref "C161") (pin "1") (pinfunction "1_1") (pintype "passive"))
      (node (ref "C162") (pin "1") (pinfunction "1_1") (pintype "passive"))
      (node (ref "C163") (pin "2") (pinfunction "2_2") (pintype "passive"))
      (node (ref "C164") (pin "1") (pinfunction "1_1") (pintype "passive"))
      (node (ref "C165") (pin "1") (pinfunction "1_1") (pintype "passive"))
      (node (ref "C166") (pin "1") (pinfunction "1_1") (pintype "passive"))
      (node (ref "C167") (pin "1") (pinfunction "1_1") (pintype "passive"))
      (node (ref "C193") (pin "1") (pinfunction "1_1") (pintype "passive"))
      (node (ref "C196") (pin "1") (pinfunction "1_1") (pintype "passive"))
      (node (ref "C197") (pin "1") (pinfunction "1_1") (pintype "passive"))
      (node (ref "C198") (pin "1") (pinfunction "1_1") (pintype "passive"))
      (node (ref "C200") (pin "1") (pinfunction "1_1") (pintype "passive"))
      (node (ref "C208") (pin "1") (pinfunction "1_1") (pintype "passive"))
      (node (ref "C211") (pin "1") (pinfunction "1_1") (pintype "passive"))
      (node (ref "C214") (pin "1") (pinfunction "1_1") (pintype "passive"))
      (node (ref "C215") (pin "1") (pinfunction "1_1") (pintype "passive"))
      (node (ref "C216") (pin "1") (pinfunction "1_1") (pintype "passive"))
      (node (ref "C221") (pin "1") (pinfunction "1_1") (pintype "passive"))
      (node (ref "C222") (pin "1") (pinfunction "1_1") (pintype "passive"))
      (node (ref "C225") (pin "1") (pinfunction "1_1") (pintype "passive"))
      (node (ref "C226") (pin "1") (pinfunction "1_1") (pintype "passive"))
      (node (ref "C227") (pin "1") (pinfunction "1_1") (pintype "passive"))
      (node (ref "C228") (pin "1") (pinfunction "1_1") (pintype "passive"))
      (node (ref "C229") (pin "1") (pinfunction "1_1") (pintype "passive"))
      (node (ref "C230") (pin "1") (pinfunction "1_1") (pintype "passive"))
      (node (ref "C231") (pin "1") (pinfunction "1_1") (pintype "passive"))
      (node (ref "C232") (pin "1") (pinfunction "1_1") (pintype "passive"))
      (node (ref "C98") (pin "1") (pinfunction "1_1") (pintype "passive"))
      (node (ref "C99") (pin "1") (pinfunction "1_1") (pintype "passive"))
      (node (ref "D1") (pin "2") (pinfunction "A_2") (pintype "passive"))
      (node (ref "IC14") (pin "2") (pinfunction "S_2") (pintype "passive"))
      (node (ref "IC15") (pin "10") (pinfunction "VSS_10") (pintype "power_in"))
      (node (ref "IC8") (pin "A1") (pinfunction "GND_A1") (pintype "power_in"))
      (node (ref "IC8") (pin "A11") (pinfunction "GND_A11") (pintype "power_in"))
      (node (ref "IC8") (pin "A16") (pinfunction "GND_A16") (pintype "power_in"))
      (node (ref "IC8") (pin "A2") (pinfunction "GND_A2") (pintype "power_in"))
      (node (ref "IC8") (pin "A21") (pinfunction "GND_A21") (pintype "power_in"))
      (node (ref "IC8") (pin "A26") (pinfunction "GND_A26") (pintype "power_in"))
      (node (ref "IC8") (pin "A5") (pinfunction "GND_A5") (pintype "power_in"))
      (node (ref "IC8") (pin "A6") (pinfunction "GND_A6") (pintype "power_in"))
      (node (ref "IC8") (pin "A8") (pinfunction "GND_A8") (pintype "power_in"))
      (node (ref "IC8") (pin "AA1") (pinfunction "GND_AA1") (pintype "power_in"))
      (node (ref "IC8") (pin "AA16") (pinfunction "GND_AA16") (pintype "power_in"))
      (node (ref "IC8") (pin "AA2") (pinfunction "GND_AA2") (pintype "power_in"))
      (node (ref "IC8") (pin "AA26") (pinfunction "GND_AA26") (pintype "power_in"))
      (node (ref "IC8") (pin "AA3") (pinfunction "GND_AA3") (pintype "power_in"))
      (node (ref "IC8") (pin "AA6") (pinfunction "GND_AA6") (pintype "power_in"))
      (node (ref "IC8") (pin "AA8") (pinfunction "GND_AA8") (pintype "power_in"))
      (node (ref "IC8") (pin "AB13") (pinfunction "GND_AB13") (pintype "power_in"))
      (node (ref "IC8") (pin "AB23") (pinfunction "GND_AB23") (pintype "power_in"))
      (node (ref "IC8") (pin "AB3") (pinfunction "GND_AB3") (pintype "power_in"))
      (node (ref "IC8") (pin "AB4") (pinfunction "GND_AB4") (pintype "power_in"))
      (node (ref "IC8") (pin "AB8") (pinfunction "GND_AB8") (pintype "power_in"))
      (node (ref "IC8") (pin "AC1") (pinfunction "GND_AC1") (pintype "power_in"))
      (node (ref "IC8") (pin "AC10") (pinfunction "GND_AC10") (pintype "power_in"))
      (node (ref "IC8") (pin "AC2") (pinfunction "GND_AC2") (pintype "power_in"))
      (node (ref "IC8") (pin "AC20") (pinfunction "GND_AC20") (pintype "power_in"))
      (node (ref "IC8") (pin "AC25") (pinfunction "GND_AC25") (pintype "power_in"))
      (node (ref "IC8") (pin "AC3") (pinfunction "GND_AC3") (pintype "power_in"))
      (node (ref "IC8") (pin "AC6") (pinfunction "GND_AC6") (pintype "power_in"))
      (node (ref "IC8") (pin "AC8") (pinfunction "GND_AC8") (pintype "power_in"))
      (node (ref "IC8") (pin "AC9") (pinfunction "GND_AC9") (pintype "power_in"))
      (node (ref "IC8") (pin "AD10") (pinfunction "GND_AD10") (pintype "power_in"))
      (node (ref "IC8") (pin "AD17") (pinfunction "GND_AD17") (pintype "power_in"))
      (node (ref "IC8") (pin "AD3") (pinfunction "GND_AD3") (pintype "power_in"))
      (node (ref "IC8") (pin "AD4") (pinfunction "GND_AD4") (pintype "power_in"))
      (node (ref "IC8") (pin "AD5") (pinfunction "GND_AD5") (pintype "power_in"))
      (node (ref "IC8") (pin "AD8") (pinfunction "MGTAVTTRCAL_R_AD8") (pintype "passive"))
      (node (ref "IC8") (pin "AD9") (pinfunction "MGTRREF_R_AD9") (pintype "input"))
      (node (ref "IC8") (pin "AE1") (pinfunction "GND_AE1") (pintype "power_in"))
      (node (ref "IC8") (pin "AE10") (pinfunction "GND_AE10") (pintype "power_in"))
      (node (ref "IC8") (pin "AE14") (pinfunction "GND_AE14") (pintype "power_in"))
      (node (ref "IC8") (pin "AE19") (pinfunction "GND_AE19") (pintype "power_in"))
      (node (ref "IC8") (pin "AE2") (pinfunction "GND_AE2") (pintype "power_in"))
      (node (ref "IC8") (pin "AE24") (pinfunction "GND_AE24") (pintype "power_in"))
      (node (ref "IC8") (pin "AE5") (pinfunction "GND_AE5") (pintype "power_in"))
      (node (ref "IC8") (pin "AE6") (pinfunction "GND_AE6") (pintype "power_in"))
      (node (ref "IC8") (pin "AF10") (pinfunction "GND_AF10") (pintype "power_in"))
      (node (ref "IC8") (pin "AF11") (pinfunction "GND_AF11") (pintype "power_in"))
      (node (ref "IC8") (pin "AF16") (pinfunction "GND_AF16") (pintype "power_in"))
      (node (ref "IC8") (pin "AF21") (pinfunction "GND_AF21") (pintype "power_in"))
      (node (ref "IC8") (pin "AF26") (pinfunction "GND_AF26") (pintype "power_in"))
      (node (ref "IC8") (pin "AF3") (pinfunction "GND_AF3") (pintype "power_in"))
      (node (ref "IC8") (pin "AF4") (pinfunction "GND_AF4") (pintype "power_in"))
      (node (ref "IC8") (pin "AF5") (pinfunction "GND_AF5") (pintype "power_in"))
      (node (ref "IC8") (pin "AF8") (pinfunction "GND_AF8") (pintype "power_in"))
      (node (ref "IC8") (pin "AF9") (pinfunction "GND_AF9") (pintype "power_in"))
      (node (ref "IC8") (pin "B13") (pinfunction "GND_B13") (pintype "power_in"))
      (node (ref "IC8") (pin "B18") (pinfunction "GND_B18") (pintype "power_in"))
      (node (ref "IC8") (pin "B23") (pinfunction "GND_B23") (pintype "power_in"))
      (node (ref "IC8") (pin "B3") (pinfunction "GND_B3") (pintype "power_in"))
      (node (ref "IC8") (pin "B4") (pinfunction "GND_B4") (pintype "power_in"))
      (node (ref "IC8") (pin "B5") (pinfunction "GND_B5") (pintype "power_in"))
      (node (ref "IC8") (pin "B8") (pinfunction "GND_B8") (pintype "power_in"))
      (node (ref "IC8") (pin "C1") (pinfunction "GND_C1") (pintype "power_in"))
      (node (ref "IC8") (pin "C10") (pinfunction "GND_C10") (pintype "power_in"))
      (node (ref "IC8") (pin "C15") (pinfunction "GND_C15") (pintype "power_in"))
      (node (ref "IC8") (pin "C2") (pinfunction "GND_C2") (pintype "power_in"))
      (node (ref "IC8") (pin "C25") (pinfunction "GND_C25") (pintype "power_in"))
      (node (ref "IC8") (pin "C5") (pinfunction "GND_C5") (pintype "power_in"))
      (node (ref "IC8") (pin "C6") (pinfunction "GND_C6") (pintype "power_in"))
      (node (ref "IC8") (pin "C8") (pinfunction "GND_C8") (pintype "power_in"))
      (node (ref "IC8") (pin "D12") (pinfunction "GND_D12") (pintype "power_in"))
      (node (ref "IC8") (pin "D22") (pinfunction "GND_D22") (pintype "power_in"))
      (node (ref "IC8") (pin "D3") (pinfunction "GND_D3") (pintype "power_in"))
      (node (ref "IC8") (pin "D4") (pinfunction "GND_D4") (pintype "power_in"))
      (node (ref "IC8") (pin "D5") (pinfunction "GND_D5") (pintype "power_in"))
      (node (ref "IC8") (pin "D8") (pinfunction "GND_D8") (pintype "power_in"))
      (node (ref "IC8") (pin "E1") (pinfunction "GND_E1") (pintype "power_in"))
      (node (ref "IC8") (pin "E19") (pinfunction "GND_E19") (pintype "power_in"))
      (node (ref "IC8") (pin "E2") (pinfunction "GND_E2") (pintype "power_in"))
      (node (ref "IC8") (pin "E3") (pinfunction "GND_E3") (pintype "power_in"))
      (node (ref "IC8") (pin "E6") (pinfunction "GND_E6") (pintype "power_in"))
      (node (ref "IC8") (pin "E8") (pinfunction "GND_E8") (pintype "power_in"))
      (node (ref "IC8") (pin "F11") (pinfunction "GND_F11") (pintype "power_in"))
      (node (ref "IC8") (pin "F16") (pinfunction "GND_F16") (pintype "power_in"))
      (node (ref "IC8") (pin "F21") (pinfunction "GND_F21") (pintype "power_in"))
      (node (ref "IC8") (pin "F26") (pinfunction "GND_F26") (pintype "power_in"))
      (node (ref "IC8") (pin "F3") (pinfunction "GND_F3") (pintype "power_in"))
      (node (ref "IC8") (pin "F4") (pinfunction "GND_F4") (pintype "power_in"))
      (node (ref "IC8") (pin "F8") (pinfunction "GND_F8") (pintype "power_in"))
      (node (ref "IC8") (pin "G1") (pinfunction "GND_G1") (pintype "power_in"))
      (node (ref "IC8") (pin "G13") (pinfunction "GND_G13") (pintype "power_in"))
      (node (ref "IC8") (pin "G2") (pinfunction "GND_G2") (pintype "power_in"))
      (node (ref "IC8") (pin "G23") (pinfunction "GND_G23") (pintype "power_in"))
      (node (ref "IC8") (pin "G3") (pinfunction "GND_G3") (pintype "power_in"))
      (node (ref "IC8") (pin "G6") (pinfunction "GND_G6") (pintype "power_in"))
      (node (ref "IC8") (pin "G8") (pinfunction "GND_G8") (pintype "power_in"))
      (node (ref "IC8") (pin "H20") (pinfunction "GND_H20") (pintype "power_in"))
      (node (ref "IC8") (pin "H3") (pinfunction "GND_H3") (pintype "power_in"))
      (node (ref "IC8") (pin "H4") (pinfunction "GND_H4") (pintype "power_in"))
      (node (ref "IC8") (pin "H8") (pinfunction "GND_H8") (pintype "power_in"))
      (node (ref "IC8") (pin "J1") (pinfunction "GND_J1") (pintype "power_in"))
      (node (ref "IC8") (pin "J17") (pinfunction "GND_J17") (pintype "power_in"))
      (node (ref "IC8") (pin "J2") (pinfunction "GND_J2") (pintype "power_in"))
      (node (ref "IC8") (pin "J3") (pinfunction "GND_J3") (pintype "power_in"))
      (node (ref "IC8") (pin "J6") (pinfunction "GND_J6") (pintype "power_in"))
      (node (ref "IC8") (pin "J8") (pinfunction "GND_J8") (pintype "power_in"))
      (node (ref "IC8") (pin "K12") (pinfunction "GND_K12") (pintype "power_in"))
      (node (ref "IC8") (pin "K14") (pinfunction "GND_K14") (pintype "power_in"))
      (node (ref "IC8") (pin "K16") (pinfunction "GND_K16") (pintype "power_in"))
      (node (ref "IC8") (pin "K19") (pinfunction "GND_K19") (pintype "power_in"))
      (node (ref "IC8") (pin "K24") (pinfunction "GND_K24") (pintype "power_in"))
      (node (ref "IC8") (pin "K3") (pinfunction "GND_K3") (pintype "power_in"))
      (node (ref "IC8") (pin "K4") (pinfunction "GND_K4") (pintype "power_in"))
      (node (ref "IC8") (pin "K8") (pinfunction "GND_K8") (pintype "power_in"))
      (node (ref "IC8") (pin "L1") (pinfunction "GND_L1") (pintype "power_in"))
      (node (ref "IC8") (pin "L11") (pinfunction "GND_L11") (pintype "power_in"))
      (node (ref "IC8") (pin "L13") (pinfunction "GND_L13") (pintype "power_in"))
      (node (ref "IC8") (pin "L15") (pinfunction "GND_L15") (pintype "power_in"))
      (node (ref "IC8") (pin "L17") (pinfunction "GND_L17") (pintype "power_in"))
      (node (ref "IC8") (pin "L2") (pinfunction "GND_L2") (pintype "power_in"))
      (node (ref "IC8") (pin "L21") (pinfunction "GND_L21") (pintype "power_in"))
      (node (ref "IC8") (pin "L26") (pinfunction "GND_L26") (pintype "power_in"))
      (node (ref "IC8") (pin "L3") (pinfunction "GND_L3") (pintype "power_in"))
      (node (ref "IC8") (pin "L6") (pinfunction "GND_L6") (pintype "power_in"))
      (node (ref "IC8") (pin "L8") (pinfunction "GND_L8") (pintype "power_in"))
      (node (ref "IC8") (pin "M10") (pinfunction "GND_M10") (pintype "power_in"))
      (node (ref "IC8") (pin "M12") (pinfunction "GND_M12") (pintype "power_in"))
      (node (ref "IC8") (pin "M14") (pinfunction "GND_M14") (pintype "power_in"))
      (node (ref "IC8") (pin "M16") (pinfunction "GND_M16") (pintype "power_in"))
      (node (ref "IC8") (pin "M23") (pinfunction "GND_M23") (pintype "power_in"))
      (node (ref "IC8") (pin "M3") (pinfunction "GND_M3") (pintype "power_in"))
      (node (ref "IC8") (pin "M4") (pinfunction "GND_M4") (pintype "power_in"))
      (node (ref "IC8") (pin "M8") (pinfunction "GND_M8") (pintype "power_in"))
      (node (ref "IC8") (pin "N1") (pinfunction "GND_N1") (pintype "power_in"))
      (node (ref "IC8") (pin "N11") (pinfunction "GND_N11") (pintype "power_in"))
      (node (ref "IC8") (pin "N15") (pinfunction "GND_N15") (pintype "power_in"))
      (node (ref "IC8") (pin "N17") (pinfunction "GND_N17") (pintype "power_in"))
      (node (ref "IC8") (pin "N2") (pinfunction "GND_N2") (pintype "power_in"))
      (node (ref "IC8") (pin "N20") (pinfunction "GND_N20") (pintype "power_in"))
      (node (ref "IC8") (pin "N25") (pinfunction "GND_N25") (pintype "power_in"))
      (node (ref "IC8") (pin "N3") (pinfunction "GND_N3") (pintype "power_in"))
      (node (ref "IC8") (pin "N6") (pinfunction "GND_N6") (pintype "power_in"))
      (node (ref "IC8") (pin "N8") (pinfunction "GND_N8") (pintype "power_in"))
      (node (ref "IC8") (pin "P10") (pinfunction "GND_P10") (pintype "power_in"))
      (node (ref "IC8") (pin "P12") (pinfunction "GND_P12") (pintype "power_in"))
      (node (ref "IC8") (pin "P16") (pinfunction "GND_P16") (pintype "power_in"))
      (node (ref "IC8") (pin "P3") (pinfunction "GND_P3") (pintype "power_in"))
      (node (ref "IC8") (pin "P4") (pinfunction "GND_P4") (pintype "power_in"))
      (node (ref "IC8") (pin "P8") (pinfunction "GND_P8") (pintype "power_in"))
      (node (ref "IC8") (pin "R1") (pinfunction "GND_R1") (pintype "power_in"))
      (node (ref "IC8") (pin "R11") (pinfunction "GND_R11") (pintype "power_in"))
      (node (ref "IC8") (pin "R15") (pinfunction "GND_R15") (pintype "power_in"))
      (node (ref "IC8") (pin "R17") (pinfunction "GND_R17") (pintype "power_in"))
      (node (ref "IC8") (pin "R19") (pinfunction "GND_R19") (pintype "power_in"))
      (node (ref "IC8") (pin "R2") (pinfunction "GND_R2") (pintype "power_in"))
      (node (ref "IC8") (pin "R24") (pinfunction "GND_R24") (pintype "power_in"))
      (node (ref "IC8") (pin "R3") (pinfunction "GND_R3") (pintype "power_in"))
      (node (ref "IC8") (pin "R6") (pinfunction "GND_R6") (pintype "power_in"))
      (node (ref "IC8") (pin "R8") (pinfunction "GND_R8") (pintype "power_in"))
      (node (ref "IC8") (pin "T10") (pinfunction "GND_T10") (pintype "power_in"))
      (node (ref "IC8") (pin "T12") (pinfunction "GND_T12") (pintype "power_in"))
      (node (ref "IC8") (pin "T13") (pinfunction "DXN_T13") (pintype "input"))
      (node (ref "IC8") (pin "T14") (pinfunction "DXP_T14") (pintype "input"))
      (node (ref "IC8") (pin "T16") (pinfunction "GND_T16") (pintype "power_in"))
      (node (ref "IC8") (pin "T21") (pinfunction "GND_T21") (pintype "power_in"))
      (node (ref "IC8") (pin "T26") (pinfunction "GND_T26") (pintype "power_in"))
      (node (ref "IC8") (pin "T3") (pinfunction "GND_T3") (pintype "power_in"))
      (node (ref "IC8") (pin "T4") (pinfunction "GND_T4") (pintype "power_in"))
      (node (ref "IC8") (pin "T8") (pinfunction "GND_T8") (pintype "power_in"))
      (node (ref "IC8") (pin "U1") (pinfunction "GND_U1") (pintype "power_in"))
      (node (ref "IC8") (pin "U11") (pinfunction "GND_U11") (pintype "power_in"))
      (node (ref "IC8") (pin "U13") (pinfunction "GND_U13") (pintype "power_in"))
      (node (ref "IC8") (pin "U15") (pinfunction "GND_U15") (pintype "power_in"))
      (node (ref "IC8") (pin "U17") (pinfunction "GND_U17") (pintype "power_in"))
      (node (ref "IC8") (pin "U18") (pinfunction "GND_U18") (pintype "power_in"))
      (node (ref "IC8") (pin "U2") (pinfunction "GND_U2") (pintype "power_in"))
      (node (ref "IC8") (pin "U3") (pinfunction "GND_U3") (pintype "power_in"))
      (node (ref "IC8") (pin "U6") (pinfunction "GND_U6") (pintype "power_in"))
      (node (ref "IC8") (pin "U8") (pinfunction "GND_U8") (pintype "power_in"))
      (node (ref "IC8") (pin "V10") (pinfunction "GND_V10") (pintype "power_in"))
      (node (ref "IC8") (pin "V12") (pinfunction "GND_V12") (pintype "power_in"))
      (node (ref "IC8") (pin "V14") (pinfunction "GND_V14") (pintype "power_in"))
      (node (ref "IC8") (pin "V16") (pinfunction "GND_V16") (pintype "power_in"))
      (node (ref "IC8") (pin "V20") (pinfunction "GND_V20") (pintype "power_in"))
      (node (ref "IC8") (pin "V25") (pinfunction "GND_V25") (pintype "power_in"))
      (node (ref "IC8") (pin "V3") (pinfunction "GND_V3") (pintype "power_in"))
      (node (ref "IC8") (pin "V4") (pinfunction "GND_V4") (pintype "power_in"))
      (node (ref "IC8") (pin "V8") (pinfunction "GND_V8") (pintype "power_in"))
      (node (ref "IC8") (pin "W1") (pinfunction "GND_W1") (pintype "power_in"))
      (node (ref "IC8") (pin "W11") (pinfunction "RSVDGND_W11") (pintype "power_in"))
      (node (ref "IC8") (pin "W17") (pinfunction "GND_W17") (pintype "power_in"))
      (node (ref "IC8") (pin "W2") (pinfunction "GND_W2") (pintype "power_in"))
      (node (ref "IC8") (pin "W22") (pinfunction "GND_W22") (pintype "power_in"))
      (node (ref "IC8") (pin "W3") (pinfunction "GND_W3") (pintype "power_in"))
      (node (ref "IC8") (pin "W6") (pinfunction "GND_W6") (pintype "power_in"))
      (node (ref "IC8") (pin "W8") (pinfunction "GND_W8") (pintype "power_in"))
      (node (ref "IC8") (pin "Y19") (pinfunction "GND_Y19") (pintype "power_in"))
      (node (ref "IC8") (pin "Y3") (pinfunction "GND_Y3") (pintype "power_in"))
      (node (ref "IC8") (pin "Y4") (pinfunction "GND_Y4") (pintype "power_in"))
      (node (ref "IC8") (pin "Y8") (pinfunction "GND_Y8") (pintype "power_in"))
      (node (ref "IC8") (pin "Y9") (pinfunction "VBATT_Y9") (pintype "power_in"))
      (node (ref "J1") (pin "1") (pinfunction "1_1") (pintype "bidirectional"))
      (node (ref "J1") (pin "11") (pinfunction "11_11") (pintype "bidirectional"))
      (node (ref "J1") (pin "13") (pinfunction "13_13") (pintype "bidirectional"))
      (node (ref "J1") (pin "3") (pinfunction "3_3") (pintype "bidirectional"))
      (node (ref "J1") (pin "5") (pinfunction "5_5") (pintype "bidirectional"))
      (node (ref "J1") (pin "7") (pinfunction "7_7") (pintype "bidirectional"))
      (node (ref "J1") (pin "9") (pinfunction "9_9") (pintype "bidirectional"))
      (node (ref "L8") (pin "2") (pinfunction "2_2") (pintype "passive"))
      (node (ref "PB1") (pin "1") (pinfunction "1_1") (pintype "bidirectional"))
      (node (ref "PB1") (pin "3") (pinfunction "3_3") (pintype "passive"))
      (node (ref "R105") (pin "1") (pinfunction "1_1") (pintype "passive"))
      (node (ref "R152") (pin "1") (pinfunction "1_1") (pintype "passive"))
      (node (ref "R153") (pin "1") (pinfunction "1_1") (pintype "passive"))
      (node (ref "R154") (pin "1") (pinfunction "1_1") (pintype "passive"))
      (node (ref "R155") (pin "1") (pinfunction "1_1") (pintype "passive"))
      (node (ref "SW1") (pin "1") (pinfunction "1_1") (pintype "bidirectional"))
      (node (ref "SW1") (pin "2") (pinfunction "2_2") (pintype "bidirectional"))
      (node (ref "SW1") (pin "3") (pinfunction "3_3") (pintype "bidirectional"))
      (node (ref "SW1") (pin "4") (pinfunction "4_4") (pintype "bidirectional"))
    )
    (net (code "27") (name "Net-(IC8K-VCCADC)") (class "Default")
      (node (ref "C233") (pin "2") (pinfunction "2_2") (pintype "passive"))
      (node (ref "C234") (pin "2") (pinfunction "2_2") (pintype "passive"))
      (node (ref "IC8") (pin "N14") (pinfunction "VCCADC_N14") (pintype "power_in"))
      (node (ref "L7") (pin "1") (pinfunction "1_1") (pintype "passive"))
    )
    (net (code "28") (name "Net-(IC8K-VREF_64)") (class "Default")
      (node (ref "IC8") (pin "W18") (pinfunction "VREF_64_W18") (pintype "power_in"))
      (node (ref "TP2") (pin "1") (pinfunction "1_1") (pintype "bidirectional"))
    )
    (net (code "29") (name "Net-(IC8K-VREF_65)") (class "Default")
      (node (ref "IC8") (pin "V18") (pinfunction "VREF_65_V18") (pintype "power_in"))
      (node (ref "TP3") (pin "1") (pinfunction "1_1") (pintype "bidirectional"))
    )
    (net (code "30") (name "Net-(IC8K-VREF_66)") (class "Default")
      (node (ref "IC8") (pin "J18") (pinfunction "VREF_66_J18") (pintype "power_in"))
      (node (ref "TP4") (pin "1") (pinfunction "1_1") (pintype "bidirectional"))
    )
    (net (code "31") (name "Net-(IC15-~{RESET})") (class "Default")
      (node (ref "IC15") (pin "3") (pinfunction "~{RESET}_3") (pintype "input"))
      (node (ref "R169") (pin "2") (pinfunction "2_2") (pintype "passive"))
    )
    (net (code "32") (name "Net-(J1-Pad14)") (class "Default")
      (node (ref "J1") (pin "14") (pinfunction "14_14") (pintype "bidirectional"))
      (node (ref "R156") (pin "1") (pinfunction "1_1") (pintype "passive"))
    )
    (net (code "33") (name "P0V85") (class "Default")
      (node (ref "C129") (pin "2") (pinfunction "2_2") (pintype "passive"))
      (node (ref "C138") (pin "2") (pinfunction "2_2") (pintype "passive"))
      (node (ref "C139") (pin "2") (pinfunction "2_2") (pintype "passive"))
      (node (ref "C140") (pin "2") (pinfunction "2_2") (pintype "passive"))
      (node (ref "C141") (pin "2") (pinfunction "2_2") (pintype "passive"))
      (node (ref "C147") (pin "2") (pinfunction "2_2") (pintype "passive"))
      (node (ref "C152") (pin "2") (pinfunction "2_2") (pintype "passive"))
      (node (ref "C157") (pin "2") (pinfunction "2_2") (pintype "passive"))
      (node (ref "C158") (pin "2") (pinfunction "2_2") (pintype "passive"))
      (node (ref "C159") (pin "2") (pinfunction "2_2") (pintype "passive"))
      (node (ref "C160") (pin "2") (pinfunction "2_2") (pintype "passive"))
      (node (ref "C161") (pin "2") (pinfunction "2_2") (pintype "passive"))
      (node (ref "C162") (pin "2") (pinfunction "2_2") (pintype "passive"))
      (node (ref "C163") (pin "1") (pinfunction "1_1") (pintype "passive"))
      (node (ref "IC8") (pin "K11") (pinfunction "VCCINT_K11") (pintype "power_in"))
      (node (ref "IC8") (pin "K13") (pinfunction "VCCINT_K13") (pintype "power_in"))
      (node (ref "IC8") (pin "K15") (pinfunction "VCCINT_K15") (pintype "power_in"))
      (node (ref "IC8") (pin "K17") (pinfunction "VCCINT_K17") (pintype "power_in"))
      (node (ref "IC8") (pin "L10") (pinfunction "VCCINT_L10") (pintype "power_in"))
      (node (ref "IC8") (pin "L12") (pinfunction "VCCINT_L12") (pintype "power_in"))
      (node (ref "IC8") (pin "L14") (pinfunction "VCCINT_L14") (pintype "power_in"))
      (node (ref "IC8") (pin "L16") (pinfunction "VCCINT_L16") (pintype "power_in"))
      (node (ref "IC8") (pin "L9") (pinfunction "VCCINT_IO_L9") (pintype "power_in"))
      (node (ref "IC8") (pin "M11") (pinfunction "VCCINT_M11") (pintype "power_in"))
      (node (ref "IC8") (pin "M13") (pinfunction "VCCINT_M13") (pintype "power_in"))
      (node (ref "IC8") (pin "M15") (pinfunction "VCCINT_M15") (pintype "power_in"))
      (node (ref "IC8") (pin "M17") (pinfunction "VCCINT_M17") (pintype "power_in"))
      (node (ref "IC8") (pin "M9") (pinfunction "VCCINT_IO_M9") (pintype "power_in"))
      (node (ref "IC8") (pin "N10") (pinfunction "VCCINT_N10") (pintype "power_in"))
      (node (ref "IC8") (pin "N12") (pinfunction "VCCINT_N12") (pintype "power_in"))
      (node (ref "IC8") (pin "N16") (pinfunction "VCCINT_N16") (pintype "power_in"))
      (node (ref "IC8") (pin "N9") (pinfunction "VCCINT_IO_N9") (pintype "power_in"))
      (node (ref "IC8") (pin "P11") (pinfunction "VCCINT_P11") (pintype "power_in"))
      (node (ref "IC8") (pin "P15") (pinfunction "VCCINT_P15") (pintype "power_in"))
      (node (ref "IC8") (pin "P17") (pinfunction "VCCINT_P17") (pintype "power_in"))
      (node (ref "IC8") (pin "P9") (pinfunction "VCCINT_IO_P9") (pintype "power_in"))
      (node (ref "IC8") (pin "R10") (pinfunction "VCCINT_R10") (pintype "power_in"))
      (node (ref "IC8") (pin "R12") (pinfunction "VCCINT_R12") (pintype "power_in"))
      (node (ref "IC8") (pin "R16") (pinfunction "VCCINT_R16") (pintype "power_in"))
      (node (ref "IC8") (pin "R9") (pinfunction "VCCBRAM_R9") (pintype "power_in"))
      (node (ref "IC8") (pin "T11") (pinfunction "VCCINT_T11") (pintype "power_in"))
      (node (ref "IC8") (pin "T15") (pinfunction "VCCINT_T15") (pintype "power_in"))
      (node (ref "IC8") (pin "T17") (pinfunction "VCCINT_T17") (pintype "power_in"))
      (node (ref "IC8") (pin "T9") (pinfunction "VCCBRAM_T9") (pintype "power_in"))
      (node (ref "IC8") (pin "U10") (pinfunction "VCCINT_U10") (pintype "power_in"))
      (node (ref "IC8") (pin "U12") (pinfunction "VCCINT_U12") (pintype "power_in"))
      (node (ref "IC8") (pin "U14") (pinfunction "VCCINT_U14") (pintype "power_in"))
      (node (ref "IC8") (pin "U16") (pinfunction "VCCINT_U16") (pintype "power_in"))
      (node (ref "IC8") (pin "U9") (pinfunction "VCCBRAM_U9") (pintype "power_in"))
      (node (ref "IC8") (pin "V11") (pinfunction "VCCINT_V11") (pintype "power_in"))
      (node (ref "IC8") (pin "V13") (pinfunction "VCCINT_V13") (pintype "power_in"))
      (node (ref "IC8") (pin "V15") (pinfunction "VCCINT_V15") (pintype "power_in"))
      (node (ref "IC8") (pin "V17") (pinfunction "VCCINT_V17") (pintype "power_in"))
      (node (ref "IC8") (pin "V9") (pinfunction "VCCBRAM_V9") (pintype "power_in"))
      (node (ref "R145") (pin "2") (pinfunction "2_2") (pintype "passive"))
    )
    (net (code "34") (name "P1V8") (class "Default")
      (node (ref "C164") (pin "2") (pinfunction "2_2") (pintype "passive"))
      (node (ref "C165") (pin "2") (pinfunction "2_2") (pintype "passive"))
      (node (ref "C166") (pin "2") (pinfunction "2_2") (pintype "passive"))
      (node (ref "C167") (pin "2") (pinfunction "2_2") (pintype "passive"))
      (node (ref "C193") (pin "2") (pinfunction "2_2") (pintype "passive"))
      (node (ref "C196") (pin "2") (pinfunction "2_2") (pintype "passive"))
      (node (ref "C222") (pin "2") (pinfunction "2_2") (pintype "passive"))
      (node (ref "C225") (pin "2") (pinfunction "2_2") (pintype "passive"))
      (node (ref "C226") (pin "2") (pinfunction "2_2") (pintype "passive"))
      (node (ref "C227") (pin "2") (pinfunction "2_2") (pintype "passive"))
      (node (ref "C228") (pin "2") (pinfunction "2_2") (pintype "passive"))
      (node (ref "C229") (pin "2") (pinfunction "2_2") (pintype "passive"))
      (node (ref "C230") (pin "2") (pinfunction "2_2") (pintype "passive"))
      (node (ref "C231") (pin "2") (pinfunction "2_2") (pintype "passive"))
      (node (ref "C232") (pin "2") (pinfunction "2_2") (pintype "passive"))
      (node (ref "C98") (pin "2") (pinfunction "2_2") (pintype "passive"))
      (node (ref "IC8") (pin "AA21") (pinfunction "VCCO_64_AA21") (pintype "power_in"))
      (node (ref "IC8") (pin "AB18") (pinfunction "VCCO_64_AB18") (pintype "power_in"))
      (node (ref "IC8") (pin "AD22") (pinfunction "VCCO_64_AD22") (pintype "power_in"))
      (node (ref "IC8") (pin "E24") (pinfunction "VCCO_66_E24") (pintype "power_in"))
      (node (ref "IC8") (pin "H25") (pinfunction "VCCO_66_H25") (pintype "power_in"))
      (node (ref "IC8") (pin "J22") (pinfunction "VCCO_66_J22") (pintype "power_in"))
      (node (ref "IC8") (pin "M18") (pinfunction "VCCAUX_M18") (pintype "power_in"))
      (node (ref "IC8") (pin "N18") (pinfunction "VCCAUX_N18") (pintype "power_in"))
      (node (ref "IC8") (pin "P18") (pinfunction "VCCAUX_IO_P18") (pintype "power_in"))
      (node (ref "IC8") (pin "P22") (pinfunction "VCCO_65_P22") (pintype "power_in"))
      (node (ref "IC8") (pin "R18") (pinfunction "VCCAUX_IO_R18") (pintype "power_in"))
      (node (ref "IC8") (pin "T18") (pinfunction "VCCAUX_IO_T18") (pintype "power_in"))
      (node (ref "IC8") (pin "U23") (pinfunction "VCCO_65_U23") (pintype "power_in"))
      (node (ref "IC8") (pin "Y24") (pinfunction "VCCO_65_Y24") (pintype "power_in"))
      (node (ref "L7") (pin "2") (pinfunction "2_2") (pintype "passive"))
    )
    (net (code "35") (name "P3V3") (class "Default")
      (node (ref "C197") (pin "2") (pinfunction "2_2") (pintype "passive"))
      (node (ref "C198") (pin "2") (pinfunction "2_2") (pintype "passive"))
      (node (ref "C200") (pin "2") (pinfunction "2_2") (pintype "passive"))
      (node (ref "C208") (pin "2") (pinfunction "2_2") (pintype "passive"))
      (node (ref "C211") (pin "2") (pinfunction "2_2") (pintype "passive"))
      (node (ref "C214") (pin "2") (pinfunction "2_2") (pintype "passive"))
      (node (ref "C215") (pin "2") (pinfunction "2_2") (pintype "passive"))
      (node (ref "C216") (pin "2") (pinfunction "2_2") (pintype "passive"))
      (node (ref "C221") (pin "2") (pinfunction "2_2") (pintype "passive"))
      (node (ref "C99") (pin "2") (pinfunction "2_2") (pintype "passive"))
      (node (ref "IC15") (pin "2") (pinfunction "VCC_2") (pintype "power_in"))
      (node (ref "IC8") (pin "AA11") (pinfunction "VCCO_0_AA11") (pintype "power_in"))
      (node (ref "IC8") (pin "AC15") (pinfunction "VCCO_84_AC15") (pintype "power_in"))
      (node (ref "IC8") (pin "AD12") (pinfunction "VCCO_0_AD12") (pintype "power_in"))
      (node (ref "IC8") (pin "E14") (pinfunction "VCCO_86_E14") (pintype "power_in"))
      (node (ref "IC8") (pin "E9") (pinfunction "VCCO_85_E9") (pintype "power_in"))
      (node (ref "IC8") (pin "H10") (pinfunction "VCCO_85_H10") (pintype "power_in"))
      (node (ref "IC8") (pin "H15") (pinfunction "VCCO_86_H15") (pintype "power_in"))
      (node (ref "IC8") (pin "Y14") (pinfunction "VCCO_84_Y14") (pintype "power_in"))
      (node (ref "J1") (pin "2") (pinfunction "2_2") (pintype "bidirectional"))
      (node (ref "R104") (pin "2") (pinfunction "2_2") (pintype "passive"))
      (node (ref "R106") (pin "2") (pinfunction "2_2") (pintype "passive"))
      (node (ref "R107") (pin "2") (pinfunction "2_2") (pintype "passive"))
      (node (ref "R108") (pin "2") (pinfunction "2_2") (pintype "passive"))
      (node (ref "R129") (pin "2") (pinfunction "2_2") (pintype "passive"))
      (node (ref "R130") (pin "2") (pinfunction "2_2") (pintype "passive"))
      (node (ref "R131") (pin "2") (pinfunction "2_2") (pintype "passive"))
      (node (ref "R144") (pin "2") (pinfunction "2_2") (pintype "passive"))
      (node (ref "R148") (pin "2") (pinfunction "2_2") (pintype "passive"))
      (node (ref "R149") (pin "2") (pinfunction "2_2") (pintype "passive"))
      (node (ref "R150") (pin "2") (pinfunction "2_2") (pintype "passive"))
      (node (ref "R156") (pin "2") (pinfunction "2_2") (pintype "passive"))
      (node (ref "R157") (pin "2") (pinfunction "2_2") (pintype "passive"))
      (node (ref "R158") (pin "2") (pinfunction "2_2") (pintype "passive"))
      (node (ref "R159") (pin "2") (pinfunction "2_2") (pintype "passive"))
      (node (ref "R164") (pin "2") (pinfunction "2_2") (pintype "passive"))
      (node (ref "R169") (pin "1") (pinfunction "1_1") (pintype "passive"))
    )
    (net (code "36") (name "unconnected-(D1E-C-Pad6)") (class "Default")
      (node (ref "D1") (pin "6") (pinfunction "C_6") (pintype "passive+no_connect"))
    )
    (net (code "37") (name "unconnected-(HS1-Pad1)") (class "Default")
      (node (ref "HS1") (pin "1") (pinfunction "1_1") (pintype "passive"))
    )
    (net (code "38") (name "unconnected-(HS1-Pad2)") (class "Default")
      (node (ref "HS1") (pin "2") (pinfunction "2_2") (pintype "passive"))
    )
    (net (code "39") (name "unconnected-(IC8H-MGTHRXN0_224-PadAF1)") (class "Default")
      (node (ref "IC8") (pin "AF1") (pinfunction "MGTHRXN0_224_AF1") (pintype "input+no_connect"))
    )
    (net (code "40") (name "unconnected-(IC8H-MGTHRXN0_225-PadY1)") (class "Default")
      (node (ref "IC8") (pin "Y1") (pinfunction "MGTHRXN0_225_Y1") (pintype "input+no_connect"))
    )
    (net (code "41") (name "unconnected-(IC8H-MGTHRXN0_226-PadM1)") (class "Default")
      (node (ref "IC8") (pin "M1") (pinfunction "MGTHRXN0_226_M1") (pintype "input+no_connect"))
    )
    (net (code "42") (name "unconnected-(IC8H-MGTHRXN1_224-PadAE3)") (class "Default")
      (node (ref "IC8") (pin "AE3") (pinfunction "MGTHRXN1_224_AE3") (pintype "input+no_connect"))
    )
    (net (code "43") (name "unconnected-(IC8H-MGTHRXN1_225-PadV1)") (class "Default")
      (node (ref "IC8") (pin "V1") (pinfunction "MGTHRXN1_225_V1") (pintype "input+no_connect"))
    )
    (net (code "44") (name "unconnected-(IC8H-MGTHRXN1_226-PadK1)") (class "Default")
      (node (ref "IC8") (pin "K1") (pinfunction "MGTHRXN1_226_K1") (pintype "input+no_connect"))
    )
    (net (code "45") (name "unconnected-(IC8H-MGTHRXN2_224-PadAD1)") (class "Default")
      (node (ref "IC8") (pin "AD1") (pinfunction "MGTHRXN2_224_AD1") (pintype "input+no_connect"))
    )
    (net (code "46") (name "unconnected-(IC8H-MGTHRXN2_225-PadT1)") (class "Default")
      (node (ref "IC8") (pin "T1") (pinfunction "MGTHRXN2_225_T1") (pintype "input+no_connect"))
    )
    (net (code "47") (name "unconnected-(IC8H-MGTHRXN2_226-PadH1)") (class "Default")
      (node (ref "IC8") (pin "H1") (pinfunction "MGTHRXN2_226_H1") (pintype "input+no_connect"))
    )
    (net (code "48") (name "unconnected-(IC8H-MGTHRXN3_224-PadAB1)") (class "Default")
      (node (ref "IC8") (pin "AB1") (pinfunction "MGTHRXN3_224_AB1") (pintype "input+no_connect"))
    )
    (net (code "49") (name "unconnected-(IC8H-MGTHRXN3_225-PadP1)") (class "Default")
      (node (ref "IC8") (pin "P1") (pinfunction "MGTHRXN3_225_P1") (pintype "input+no_connect"))
    )
    (net (code "50") (name "unconnected-(IC8H-MGTHRXN3_226-PadF1)") (class "Default")
      (node (ref "IC8") (pin "F1") (pinfunction "MGTHRXN3_226_F1") (pintype "input+no_connect"))
    )
    (net (code "51") (name "unconnected-(IC8H-MGTHRXP0_224-PadAF2)") (class "Default")
      (node (ref "IC8") (pin "AF2") (pinfunction "MGTHRXP0_224_AF2") (pintype "input+no_connect"))
    )
    (net (code "52") (name "unconnected-(IC8H-MGTHRXP0_225-PadY2)") (class "Default")
      (node (ref "IC8") (pin "Y2") (pinfunction "MGTHRXP0_225_Y2") (pintype "input+no_connect"))
    )
    (net (code "53") (name "unconnected-(IC8H-MGTHRXP0_226-PadM2)") (class "Default")
      (node (ref "IC8") (pin "M2") (pinfunction "MGTHRXP0_226_M2") (pintype "input+no_connect"))
    )
    (net (code "54") (name "unconnected-(IC8H-MGTHRXP1_224-PadAE4)") (class "Default")
      (node (ref "IC8") (pin "AE4") (pinfunction "MGTHRXP1_224_AE4") (pintype "input+no_connect"))
    )
    (net (code "55") (name "unconnected-(IC8H-MGTHRXP1_225-PadV2)") (class "Default")
      (node (ref "IC8") (pin "V2") (pinfunction "MGTHRXP1_225_V2") (pintype "input+no_connect"))
    )
    (net (code "56") (name "unconnected-(IC8H-MGTHRXP1_226-PadK2)") (class "Default")
      (node (ref "IC8") (pin "K2") (pinfunction "MGTHRXP1_226_K2") (pintype "input+no_connect"))
    )
    (net (code "57") (name "unconnected-(IC8H-MGTHRXP2_224-PadAD2)") (class "Default")
      (node (ref "IC8") (pin "AD2") (pinfunction "MGTHRXP2_224_AD2") (pintype "input+no_connect"))
    )
    (net (code "58") (name "unconnected-(IC8H-MGTHRXP2_225-PadT2)") (class "Default")
      (node (ref "IC8") (pin "T2") (pinfunction "MGTHRXP2_225_T2") (pintype "input+no_connect"))
    )
    (net (code "59") (name "unconnected-(IC8H-MGTHRXP2_226-PadH2)") (class "Default")
      (node (ref "IC8") (pin "H2") (pinfunction "MGTHRXP2_226_H2") (pintype "input+no_connect"))
    )
    (net (code "60") (name "unconnected-(IC8H-MGTHRXP3_224-PadAB2)") (class "Default")
      (node (ref "IC8") (pin "AB2") (pinfunction "MGTHRXP3_224_AB2") (pintype "input+no_connect"))
    )
    (net (code "61") (name "unconnected-(IC8H-MGTHRXP3_225-PadP2)") (class "Default")
      (node (ref "IC8") (pin "P2") (pinfunction "MGTHRXP3_225_P2") (pintype "input+no_connect"))
    )
    (net (code "62") (name "unconnected-(IC8H-MGTHRXP3_226-PadF2)") (class "Default")
      (node (ref "IC8") (pin "F2") (pinfunction "MGTHRXP3_226_F2") (pintype "input+no_connect"))
    )
    (net (code "63") (name "unconnected-(IC8H-MGTHTXN0_224-PadAF6)") (class "Default")
      (node (ref "IC8") (pin "AF6") (pinfunction "MGTHTXN0_224_AF6") (pintype "output"))
    )
    (net (code "64") (name "unconnected-(IC8H-MGTHTXN0_225-PadAA4)") (class "Default")
      (node (ref "IC8") (pin "AA4") (pinfunction "MGTHTXN0_225_AA4") (pintype "output"))
    )
    (net (code "65") (name "unconnected-(IC8H-MGTHTXN0_226-PadN4)") (class "Default")
      (node (ref "IC8") (pin "N4") (pinfunction "MGTHTXN0_226_N4") (pintype "output"))
    )
    (net (code "66") (name "unconnected-(IC8H-MGTHTXN1_224-PadAE8)") (class "Default")
      (node (ref "IC8") (pin "AE8") (pinfunction "MGTHTXN1_224_AE8") (pintype "output"))
    )
    (net (code "67") (name "unconnected-(IC8H-MGTHTXN1_225-PadW4)") (class "Default")
      (node (ref "IC8") (pin "W4") (pinfunction "MGTHTXN1_225_W4") (pintype "output"))
    )
    (net (code "68") (name "unconnected-(IC8H-MGTHTXN1_226-PadL4)") (class "Default")
      (node (ref "IC8") (pin "L4") (pinfunction "MGTHTXN1_226_L4") (pintype "output"))
    )
    (net (code "69") (name "unconnected-(IC8H-MGTHTXN2_224-PadAD6)") (class "Default")
      (node (ref "IC8") (pin "AD6") (pinfunction "MGTHTXN2_224_AD6") (pintype "output"))
    )
    (net (code "70") (name "unconnected-(IC8H-MGTHTXN2_225-PadU4)") (class "Default")
      (node (ref "IC8") (pin "U4") (pinfunction "MGTHTXN2_225_U4") (pintype "output"))
    )
    (net (code "71") (name "unconnected-(IC8H-MGTHTXN2_226-PadJ4)") (class "Default")
      (node (ref "IC8") (pin "J4") (pinfunction "MGTHTXN2_226_J4") (pintype "output"))
    )
    (net (code "72") (name "unconnected-(IC8H-MGTHTXN3_224-PadAC4)") (class "Default")
      (node (ref "IC8") (pin "AC4") (pinfunction "MGTHTXN3_224_AC4") (pintype "output"))
    )
    (net (code "73") (name "unconnected-(IC8H-MGTHTXN3_225-PadR4)") (class "Default")
      (node (ref "IC8") (pin "R4") (pinfunction "MGTHTXN3_225_R4") (pintype "output"))
    )
    (net (code "74") (name "unconnected-(IC8H-MGTHTXN3_226-PadG4)") (class "Default")
      (node (ref "IC8") (pin "G4") (pinfunction "MGTHTXN3_226_G4") (pintype "output"))
    )
    (net (code "75") (name "unconnected-(IC8H-MGTHTXP0_224-PadAF7)") (class "Default")
      (node (ref "IC8") (pin "AF7") (pinfunction "MGTHTXP0_224_AF7") (pintype "output"))
    )
    (net (code "76") (name "unconnected-(IC8H-MGTHTXP0_225-PadAA5)") (class "Default")
      (node (ref "IC8") (pin "AA5") (pinfunction "MGTHTXP0_225_AA5") (pintype "output"))
    )
    (net (code "77") (name "unconnected-(IC8H-MGTHTXP0_226-PadN5)") (class "Default")
      (node (ref "IC8") (pin "N5") (pinfunction "MGTHTXP0_226_N5") (pintype "output"))
    )
    (net (code "78") (name "unconnected-(IC8H-MGTHTXP1_224-PadAE9)") (class "Default")
      (node (ref "IC8") (pin "AE9") (pinfunction "MGTHTXP1_224_AE9") (pintype "output"))
    )
    (net (code "79") (name "unconnected-(IC8H-MGTHTXP1_225-PadW5)") (class "Default")
      (node (ref "IC8") (pin "W5") (pinfunction "MGTHTXP1_225_W5") (pintype "output"))
    )
    (net (code "80") (name "unconnected-(IC8H-MGTHTXP1_226-PadL5)") (class "Default")
      (node (ref "IC8") (pin "L5") (pinfunction "MGTHTXP1_226_L5") (pintype "output"))
    )
    (net (code "81") (name "unconnected-(IC8H-MGTHTXP2_224-PadAD7)") (class "Default")
      (node (ref "IC8") (pin "AD7") (pinfunction "MGTHTXP2_224_AD7") (pintype "output"))
    )
    (net (code "82") (name "unconnected-(IC8H-MGTHTXP2_225-PadU5)") (class "Default")
      (node (ref "IC8") (pin "U5") (pinfunction "MGTHTXP2_225_U5") (pintype "output"))
    )
    (net (code "83") (name "unconnected-(IC8H-MGTHTXP2_226-PadJ5)") (class "Default")
      (node (ref "IC8") (pin "J5") (pinfunction "MGTHTXP2_226_J5") (pintype "output"))
    )
    (net (code "84") (name "unconnected-(IC8H-MGTHTXP3_224-PadAC5)") (class "Default")
      (node (ref "IC8") (pin "AC5") (pinfunction "MGTHTXP3_224_AC5") (pintype "output"))
    )
    (net (code "85") (name "unconnected-(IC8H-MGTHTXP3_225-PadR5)") (class "Default")
      (node (ref "IC8") (pin "R5") (pinfunction "MGTHTXP3_225_R5") (pintype "output"))
    )
    (net (code "86") (name "unconnected-(IC8H-MGTHTXP3_226-PadG5)") (class "Default")
      (node (ref "IC8") (pin "G5") (pinfunction "MGTHTXP3_226_G5") (pintype "output"))
    )
    (net (code "87") (name "unconnected-(IC8H-MGTREFCLK0N_224-PadAB6)") (class "Default")
      (node (ref "IC8") (pin "AB6") (pinfunction "MGTREFCLK0N_224_AB6") (pintype "input+no_connect"))
    )
    (net (code "88") (name "unconnected-(IC8H-MGTREFCLK0N_225-PadV6)") (class "Default")
      (node (ref "IC8") (pin "V6") (pinfunction "MGTREFCLK0N_225_V6") (pintype "input+no_connect"))
    )
    (net (code "89") (name "unconnected-(IC8H-MGTREFCLK0N_226-PadP6)") (class "Default")
      (node (ref "IC8") (pin "P6") (pinfunction "MGTREFCLK0N_226_P6") (pintype "input+no_connect"))
    )
    (net (code "90") (name "unconnected-(IC8H-MGTREFCLK0P_224-PadAB7)") (class "Default")
      (node (ref "IC8") (pin "AB7") (pinfunction "MGTREFCLK0P_224_AB7") (pintype "input+no_connect"))
    )
    (net (code "91") (name "unconnected-(IC8H-MGTREFCLK0P_225-PadV7)") (class "Default")
      (node (ref "IC8") (pin "V7") (pinfunction "MGTREFCLK0P_225_V7") (pintype "input+no_connect"))
    )
    (net (code "92") (name "unconnected-(IC8H-MGTREFCLK0P_226-PadP7)") (class "Default")
      (node (ref "IC8") (pin "P7") (pinfunction "MGTREFCLK0P_226_P7") (pintype "input+no_connect"))
    )
    (net (code "93") (name "unconnected-(IC8H-MGTREFCLK1N_224-PadY6)") (class "Default")
      (node (ref "IC8") (pin "Y6") (pinfunction "MGTREFCLK1N_224_Y6") (pintype "input+no_connect"))
    )
    (net (code "94") (name "unconnected-(IC8H-MGTREFCLK1N_225-PadT6)") (class "Default")
      (node (ref "IC8") (pin "T6") (pinfunction "MGTREFCLK1N_225_T6") (pintype "input+no_connect"))
    )
    (net (code "95") (name "unconnected-(IC8H-MGTREFCLK1N_226-PadM6)") (class "Default")
      (node (ref "IC8") (pin "M6") (pinfunction "MGTREFCLK1N_226_M6") (pintype "input+no_connect"))
    )
    (net (code "96") (name "unconnected-(IC8H-MGTREFCLK1P_224-PadY7)") (class "Default")
      (node (ref "IC8") (pin "Y7") (pinfunction "MGTREFCLK1P_224_Y7") (pintype "input+no_connect"))
    )
    (net (code "97") (name "unconnected-(IC8H-MGTREFCLK1P_225-PadT7)") (class "Default")
      (node (ref "IC8") (pin "T7") (pinfunction "MGTREFCLK1P_225_T7") (pintype "input+no_connect"))
    )
    (net (code "98") (name "unconnected-(IC8H-MGTREFCLK1P_226-PadM7)") (class "Default")
      (node (ref "IC8") (pin "M7") (pinfunction "MGTREFCLK1P_226_M7") (pintype "input+no_connect"))
    )
    (net (code "99") (name "unconnected-(IC8I-MGTAVCC_R-PadAA7)") (class "Default")
      (node (ref "IC8") (pin "AA7") (pinfunction "MGTAVCC_R_AA7") (pintype "power_in"))
    )
    (net (code "100") (name "unconnected-(IC8I-MGTAVCC_R-PadAC7)") (class "Default")
      (node (ref "IC8") (pin "AC7") (pinfunction "MGTAVCC_R_AC7") (pintype "power_in"))
    )
    (net (code "101") (name "unconnected-(IC8I-MGTAVCC_R-PadJ7)") (class "Default")
      (node (ref "IC8") (pin "J7") (pinfunction "MGTAVCC_R_J7") (pintype "power_in"))
    )
    (net (code "102") (name "unconnected-(IC8I-MGTAVCC_R-PadL7)") (class "Default")
      (node (ref "IC8") (pin "L7") (pinfunction "MGTAVCC_R_L7") (pintype "power_in"))
    )
    (net (code "103") (name "unconnected-(IC8I-MGTAVCC_R-PadN7)") (class "Default")
      (node (ref "IC8") (pin "N7") (pinfunction "MGTAVCC_R_N7") (pintype "power_in"))
    )
    (net (code "104") (name "unconnected-(IC8I-MGTAVCC_R-PadW7)") (class "Default")
      (node (ref "IC8") (pin "W7") (pinfunction "MGTAVCC_R_W7") (pintype "power_in"))
    )
    (net (code "105") (name "unconnected-(IC8I-MGTAVTT_R-PadA7)") (class "Default")
      (node (ref "IC8") (pin "A7") (pinfunction "MGTAVTT_R_A7") (pintype "power_in"))
    )
    (net (code "106") (name "unconnected-(IC8I-MGTAVTT_R-PadAB5)") (class "Default")
      (node (ref "IC8") (pin "AB5") (pinfunction "MGTAVTT_R_AB5") (pintype "power_in"))
    )
    (net (code "107") (name "unconnected-(IC8I-MGTAVTT_R-PadAE7)") (class "Default")
      (node (ref "IC8") (pin "AE7") (pinfunction "MGTAVTT_R_AE7") (pintype "power_in"))
    )
    (net (code "108") (name "unconnected-(IC8I-MGTAVTT_R-PadC7)") (class "Default")
      (node (ref "IC8") (pin "C7") (pinfunction "MGTAVTT_R_C7") (pintype "power_in"))
    )
    (net (code "109") (name "unconnected-(IC8I-MGTAVTT_R-PadE7)") (class "Default")
      (node (ref "IC8") (pin "E7") (pinfunction "MGTAVTT_R_E7") (pintype "power_in"))
    )
    (net (code "110") (name "unconnected-(IC8I-MGTAVTT_R-PadF5)") (class "Default")
      (node (ref "IC8") (pin "F5") (pinfunction "MGTAVTT_R_F5") (pintype "power_in"))
    )
    (net (code "111") (name "unconnected-(IC8I-MGTAVTT_R-PadG7)") (class "Default")
      (node (ref "IC8") (pin "G7") (pinfunction "MGTAVTT_R_G7") (pintype "power_in"))
    )
    (net (code "112") (name "unconnected-(IC8I-MGTAVTT_R-PadH5)") (class "Default")
      (node (ref "IC8") (pin "H5") (pinfunction "MGTAVTT_R_H5") (pintype "power_in"))
    )
    (net (code "113") (name "unconnected-(IC8I-MGTAVTT_R-PadK5)") (class "Default")
      (node (ref "IC8") (pin "K5") (pinfunction "MGTAVTT_R_K5") (pintype "power_in"))
    )
    (net (code "114") (name "unconnected-(IC8I-MGTAVTT_R-PadM5)") (class "Default")
      (node (ref "IC8") (pin "M5") (pinfunction "MGTAVTT_R_M5") (pintype "power_in"))
    )
    (net (code "115") (name "unconnected-(IC8I-MGTAVTT_R-PadP5)") (class "Default")
      (node (ref "IC8") (pin "P5") (pinfunction "MGTAVTT_R_P5") (pintype "power_in"))
    )
    (net (code "116") (name "unconnected-(IC8I-MGTAVTT_R-PadT5)") (class "Default")
      (node (ref "IC8") (pin "T5") (pinfunction "MGTAVTT_R_T5") (pintype "power_in"))
    )
    (net (code "117") (name "unconnected-(IC8I-MGTAVTT_R-PadV5)") (class "Default")
      (node (ref "IC8") (pin "V5") (pinfunction "MGTAVTT_R_V5") (pintype "power_in"))
    )
    (net (code "118") (name "unconnected-(IC8I-MGTAVTT_R-PadY5)") (class "Default")
      (node (ref "IC8") (pin "Y5") (pinfunction "MGTAVTT_R_Y5") (pintype "power_in"))
    )
    (net (code "119") (name "unconnected-(IC8I-MGTVCCAUX_R-PadR7)") (class "Default")
      (node (ref "IC8") (pin "R7") (pinfunction "MGTVCCAUX_R_R7") (pintype "power_in"))
    )
    (net (code "120") (name "unconnected-(IC8I-MGTVCCAUX_R-PadU7)") (class "Default")
      (node (ref "IC8") (pin "U7") (pinfunction "MGTVCCAUX_R_U7") (pintype "power_in"))
    )
    (net (code "121") (name "unconnected-(IC8L-NC-PadA3)") (class "Default")
      (node (ref "IC8") (pin "A3") (pinfunction "NC_A3") (pintype "passive"))
    )
    (net (code "122") (name "unconnected-(IC8L-NC-PadA4)") (class "Default")
      (node (ref "IC8") (pin "A4") (pinfunction "NC_A4") (pintype "passive"))
    )
    (net (code "123") (name "unconnected-(IC8L-NC-PadA15)") (class "Default")
      (node (ref "IC8") (pin "A15") (pinfunction "NC_A15") (pintype "passive"))
    )
    (net (code "124") (name "unconnected-(IC8L-NC-PadA17)") (class "Default")
      (node (ref "IC8") (pin "A17") (pinfunction "NC_A17") (pintype "passive"))
    )
    (net (code "125") (name "unconnected-(IC8L-NC-PadA18)") (class "Default")
      (node (ref "IC8") (pin "A18") (pinfunction "NC_A18") (pintype "passive"))
    )
    (net (code "126") (name "unconnected-(IC8L-NC-PadA19)") (class "Default")
      (node (ref "IC8") (pin "A19") (pinfunction "NC_A19") (pintype "passive"))
    )
    (net (code "127") (name "unconnected-(IC8L-NC-PadA20)") (class "Default")
      (node (ref "IC8") (pin "A20") (pinfunction "NC_A20") (pintype "passive"))
    )
    (net (code "128") (name "unconnected-(IC8L-NC-PadA22)") (class "Default")
      (node (ref "IC8") (pin "A22") (pinfunction "NC_A22") (pintype "passive"))
    )
    (net (code "129") (name "unconnected-(IC8L-NC-PadA23)") (class "Default")
      (node (ref "IC8") (pin "A23") (pinfunction "NC_A23") (pintype "passive"))
    )
    (net (code "130") (name "unconnected-(IC8L-NC-PadA24)") (class "Default")
      (node (ref "IC8") (pin "A24") (pinfunction "NC_A24") (pintype "passive"))
    )
    (net (code "131") (name "unconnected-(IC8L-NC-PadA25)") (class "Default")
      (node (ref "IC8") (pin "A25") (pinfunction "NC_A25") (pintype "passive"))
    )
    (net (code "132") (name "unconnected-(IC8L-NC-PadB1)") (class "Default")
      (node (ref "IC8") (pin "B1") (pinfunction "NC_B1") (pintype "passive"))
    )
    (net (code "133") (name "unconnected-(IC8L-NC-PadB2)") (class "Default")
      (node (ref "IC8") (pin "B2") (pinfunction "NC_B2") (pintype "passive"))
    )
    (net (code "134") (name "unconnected-(IC8L-NC-PadB6)") (class "Default")
      (node (ref "IC8") (pin "B6") (pinfunction "NC_B6") (pintype "passive"))
    )
    (net (code "135") (name "unconnected-(IC8L-NC-PadB7)") (class "Default")
      (node (ref "IC8") (pin "B7") (pinfunction "NC_B7") (pintype "passive"))
    )
    (net (code "136") (name "unconnected-(IC8L-NC-PadB15)") (class "Default")
      (node (ref "IC8") (pin "B15") (pinfunction "NC_B15") (pintype "passive"))
    )
    (net (code "137") (name "unconnected-(IC8L-NC-PadB16)") (class "Default")
      (node (ref "IC8") (pin "B16") (pinfunction "NC_B16") (pintype "passive"))
    )
    (net (code "138") (name "unconnected-(IC8L-NC-PadB17)") (class "Default")
      (node (ref "IC8") (pin "B17") (pinfunction "NC_B17") (pintype "passive"))
    )
    (net (code "139") (name "unconnected-(IC8L-NC-PadB19)") (class "Default")
      (node (ref "IC8") (pin "B19") (pinfunction "NC_B19") (pintype "passive"))
    )
    (net (code "140") (name "unconnected-(IC8L-NC-PadB20)") (class "Default")
      (node (ref "IC8") (pin "B20") (pinfunction "NC_B20") (pintype "passive"))
    )
    (net (code "141") (name "unconnected-(IC8L-NC-PadB21)") (class "Default")
      (node (ref "IC8") (pin "B21") (pinfunction "NC_B21") (pintype "passive"))
    )
    (net (code "142") (name "unconnected-(IC8L-NC-PadB22)") (class "Default")
      (node (ref "IC8") (pin "B22") (pinfunction "NC_B22") (pintype "passive"))
    )
    (net (code "143") (name "unconnected-(IC8L-NC-PadB24)") (class "Default")
      (node (ref "IC8") (pin "B24") (pinfunction "NC_B24") (pintype "passive"))
    )
    (net (code "144") (name "unconnected-(IC8L-NC-PadC3)") (class "Default")
      (node (ref "IC8") (pin "C3") (pinfunction "NC_C3") (pintype "passive"))
    )
    (net (code "145") (name "unconnected-(IC8L-NC-PadC4)") (class "Default")
      (node (ref "IC8") (pin "C4") (pinfunction "NC_C4") (pintype "passive"))
    )
    (net (code "146") (name "unconnected-(IC8L-NC-PadC16)") (class "Default")
      (node (ref "IC8") (pin "C16") (pinfunction "NC_C16") (pintype "passive"))
    )
    (net (code "147") (name "unconnected-(IC8L-NC-PadC17)") (class "Default")
      (node (ref "IC8") (pin "C17") (pinfunction "NC_C17") (pintype "passive"))
    )
    (net (code "148") (name "unconnected-(IC8L-NC-PadC18)") (class "Default")
      (node (ref "IC8") (pin "C18") (pinfunction "NC_C18") (pintype "passive"))
    )
    (net (code "149") (name "unconnected-(IC8L-NC-PadC19)") (class "Default")
      (node (ref "IC8") (pin "C19") (pinfunction "NC_C19") (pintype "passive"))
    )
    (net (code "150") (name "unconnected-(IC8L-NC-PadC20)") (class "Default")
      (node (ref "IC8") (pin "C20") (pinfunction "NC_C20") (pintype "passive"))
    )
    (net (code "151") (name "unconnected-(IC8L-NC-PadC21)") (class "Default")
      (node (ref "IC8") (pin "C21") (pinfunction "NC_C21") (pintype "passive"))
    )
    (net (code "152") (name "unconnected-(IC8L-NC-PadC22)") (class "Default")
      (node (ref "IC8") (pin "C22") (pinfunction "NC_C22") (pintype "passive"))
    )
    (net (code "153") (name "unconnected-(IC8L-NC-PadC23)") (class "Default")
      (node (ref "IC8") (pin "C23") (pinfunction "NC_C23") (pintype "passive"))
    )
    (net (code "154") (name "unconnected-(IC8L-NC-PadD1)") (class "Default")
      (node (ref "IC8") (pin "D1") (pinfunction "NC_D1") (pintype "passive"))
    )
    (net (code "155") (name "unconnected-(IC8L-NC-PadD2)") (class "Default")
      (node (ref "IC8") (pin "D2") (pinfunction "NC_D2") (pintype "passive"))
    )
    (net (code "156") (name "unconnected-(IC8L-NC-PadD6)") (class "Default")
      (node (ref "IC8") (pin "D6") (pinfunction "NC_D6") (pintype "passive"))
    )
    (net (code "157") (name "unconnected-(IC8L-NC-PadD7)") (class "Default")
      (node (ref "IC8") (pin "D7") (pinfunction "NC_D7") (pintype "passive"))
    )
    (net (code "158") (name "unconnected-(IC8L-NC-PadD15)") (class "Default")
      (node (ref "IC8") (pin "D15") (pinfunction "NC_D15") (pintype "passive"))
    )
    (net (code "159") (name "unconnected-(IC8L-NC-PadD16)") (class "Default")
      (node (ref "IC8") (pin "D16") (pinfunction "NC_D16") (pintype "passive"))
    )
    (net (code "160") (name "unconnected-(IC8L-NC-PadD17)") (class "Default")
      (node (ref "IC8") (pin "D17") (pinfunction "NC_D17") (pintype "passive"))
    )
    (net (code "161") (name "unconnected-(IC8L-NC-PadD18)") (class "Default")
      (node (ref "IC8") (pin "D18") (pinfunction "NC_D18") (pintype "passive"))
    )
    (net (code "162") (name "unconnected-(IC8L-NC-PadD19)") (class "Default")
      (node (ref "IC8") (pin "D19") (pinfunction "NC_D19") (pintype "passive"))
    )
    (net (code "163") (name "unconnected-(IC8L-NC-PadD20)") (class "Default")
      (node (ref "IC8") (pin "D20") (pinfunction "NC_D20") (pintype "passive"))
    )
    (net (code "164") (name "unconnected-(IC8L-NC-PadD21)") (class "Default")
      (node (ref "IC8") (pin "D21") (pinfunction "NC_D21") (pintype "passive"))
    )
    (net (code "165") (name "unconnected-(IC8L-NC-PadE4)") (class "Default")
      (node (ref "IC8") (pin "E4") (pinfunction "NC_E4") (pintype "passive"))
    )
    (net (code "166") (name "unconnected-(IC8L-NC-PadE5)") (class "Default")
      (node (ref "IC8") (pin "E5") (pinfunction "NC_E5") (pintype "passive"))
    )
    (net (code "167") (name "unconnected-(IC8L-NC-PadE15)") (class "Default")
      (node (ref "IC8") (pin "E15") (pinfunction "NC_E15") (pintype "passive"))
    )
    (net (code "168") (name "unconnected-(IC8L-NC-PadE16)") (class "Default")
      (node (ref "IC8") (pin "E16") (pinfunction "NC_E16") (pintype "passive"))
    )
    (net (code "169") (name "unconnected-(IC8L-NC-PadE17)") (class "Default")
      (node (ref "IC8") (pin "E17") (pinfunction "NC_E17") (pintype "passive"))
    )
    (net (code "170") (name "unconnected-(IC8L-NC-PadE18)") (class "Default")
      (node (ref "IC8") (pin "E18") (pinfunction "NC_E18") (pintype "passive"))
    )
    (net (code "171") (name "unconnected-(IC8L-NC-PadE20)") (class "Default")
      (node (ref "IC8") (pin "E20") (pinfunction "NC_E20") (pintype "passive"))
    )
    (net (code "172") (name "unconnected-(IC8L-NC-PadE21)") (class "Default")
      (node (ref "IC8") (pin "E21") (pinfunction "NC_E21") (pintype "passive"))
    )
    (net (code "173") (name "unconnected-(IC8L-NC-PadE22)") (class "Default")
      (node (ref "IC8") (pin "E22") (pinfunction "NC_E22") (pintype "passive"))
    )
    (net (code "174") (name "unconnected-(IC8L-NC-PadF6)") (class "Default")
      (node (ref "IC8") (pin "F6") (pinfunction "NC_F6") (pintype "passive"))
    )
    (net (code "175") (name "unconnected-(IC8L-NC-PadF7)") (class "Default")
      (node (ref "IC8") (pin "F7") (pinfunction "NC_F7") (pintype "passive"))
    )
    (net (code "176") (name "unconnected-(IC8L-NC-PadF15)") (class "Default")
      (node (ref "IC8") (pin "F15") (pinfunction "NC_F15") (pintype "passive"))
    )
    (net (code "177") (name "unconnected-(IC8L-NC-PadF17)") (class "Default")
      (node (ref "IC8") (pin "F17") (pinfunction "NC_F17") (pintype "passive"))
    )
    (net (code "178") (name "unconnected-(IC8L-NC-PadF18)") (class "Default")
      (node (ref "IC8") (pin "F18") (pinfunction "NC_F18") (pintype "passive"))
    )
    (net (code "179") (name "unconnected-(IC8L-NC-PadF19)") (class "Default")
      (node (ref "IC8") (pin "F19") (pinfunction "NC_F19") (pintype "passive"))
    )
    (net (code "180") (name "unconnected-(IC8L-NC-PadF20)") (class "Default")
      (node (ref "IC8") (pin "F20") (pinfunction "NC_F20") (pintype "passive"))
    )
    (net (code "181") (name "unconnected-(IC8L-NC-PadG15)") (class "Default")
      (node (ref "IC8") (pin "G15") (pinfunction "NC_G15") (pintype "passive"))
    )
    (net (code "182") (name "unconnected-(IC8L-NC-PadG16)") (class "Default")
      (node (ref "IC8") (pin "G16") (pinfunction "NC_G16") (pintype "passive"))
    )
    (net (code "183") (name "unconnected-(IC8L-NC-PadG17)") (class "Default")
      (node (ref "IC8") (pin "G17") (pinfunction "NC_G17") (pintype "passive"))
    )
    (net (code "184") (name "unconnected-(IC8L-NC-PadG18)") (class "Default")
      (node (ref "IC8") (pin "G18") (pinfunction "NC_G18") (pintype "passive"))
    )
    (net (code "185") (name "unconnected-(IC8L-NC-PadG19)") (class "Default")
      (node (ref "IC8") (pin "G19") (pinfunction "NC_G19") (pintype "passive"))
    )
    (net (code "186") (name "unconnected-(IC8L-NC-PadG20)") (class "Default")
      (node (ref "IC8") (pin "G20") (pinfunction "NC_G20") (pintype "passive"))
    )
    (net (code "187") (name "unconnected-(IC8L-NC-PadG21)") (class "Default")
      (node (ref "IC8") (pin "G21") (pinfunction "NC_G21") (pintype "passive"))
    )
    (net (code "188") (name "unconnected-(IC8L-NC-PadH6)") (class "Default")
      (node (ref "IC8") (pin "H6") (pinfunction "NC_H6") (pintype "passive"))
    )
    (net (code "189") (name "unconnected-(IC8L-NC-PadH7)") (class "Default")
      (node (ref "IC8") (pin "H7") (pinfunction "NC_H7") (pintype "passive"))
    )
    (net (code "190") (name "unconnected-(IC8L-NC-PadH16)") (class "Default")
      (node (ref "IC8") (pin "H16") (pinfunction "NC_H16") (pintype "passive"))
    )
    (net (code "191") (name "unconnected-(IC8L-NC-PadH17)") (class "Default")
      (node (ref "IC8") (pin "H17") (pinfunction "NC_H17") (pintype "passive"))
    )
    (net (code "192") (name "unconnected-(IC8L-NC-PadH18)") (class "Default")
      (node (ref "IC8") (pin "H18") (pinfunction "NC_H18") (pintype "passive"))
    )
    (net (code "193") (name "unconnected-(IC8L-NC-PadH19)") (class "Default")
      (node (ref "IC8") (pin "H19") (pinfunction "NC_H19") (pintype "passive"))
    )
    (net (code "194") (name "unconnected-(IC8L-NC-PadJ16)") (class "Default")
      (node (ref "IC8") (pin "J16") (pinfunction "NC_J16") (pintype "passive"))
    )
    (net (code "195") (name "unconnected-(IC8L-NC-PadK6)") (class "Default")
      (node (ref "IC8") (pin "K6") (pinfunction "NC_K6") (pintype "passive"))
    )
    (net (code "196") (name "unconnected-(IC8L-NC-PadK7)") (class "Default")
      (node (ref "IC8") (pin "K7") (pinfunction "NC_K7") (pintype "passive"))
    )
    (net (code "197") (name "unconnected-(IC15-DNU-Pad4)") (class "Default")
      (node (ref "IC15") (pin "4") (pinfunction "DNU_4") (pintype "passive+no_connect"))
    )
    (net (code "198") (name "unconnected-(IC15-DNU-Pad5)") (class "Default")
      (node (ref "IC15") (pin "5") (pinfunction "DNU_5") (pintype "passive+no_connect"))
    )
    (net (code "199") (name "unconnected-(IC15-DNU-Pad6)") (class "Default")
      (node (ref "IC15") (pin "6") (pinfunction "DNU_6") (pintype "passive+no_connect"))
    )
    (net (code "200") (name "unconnected-(IC15-DNU-Pad11)") (class "Default")
      (node (ref "IC15") (pin "11") (pinfunction "DNU_11") (pintype "passive+no_connect"))
    )
    (net (code "201") (name "unconnected-(IC15-DNU-Pad12)") (class "Default")
      (node (ref "IC15") (pin "12") (pinfunction "DNU_12") (pintype "passive+no_connect"))
    )
    (net (code "202") (name "unconnected-(IC15-DNU-Pad13)") (class "Default")
      (node (ref "IC15") (pin "13") (pinfunction "DNU_13") (pintype "passive+no_connect"))
    )
    (net (code "203") (name "unconnected-(IC15-DNU-Pad14)") (class "Default")
      (node (ref "IC15") (pin "14") (pinfunction "DNU_14") (pintype "passive+no_connect"))
    )
    (net (code "204") (name "unconnected-(J1-Pad12)") (class "Default")
      (node (ref "J1") (pin "12") (pinfunction "12_12") (pintype "bidirectional+no_connect"))
    )
  )
)
